# microzed_breakout_v0_7.net
KiCad netlist of a schematic drawn in EAGLE
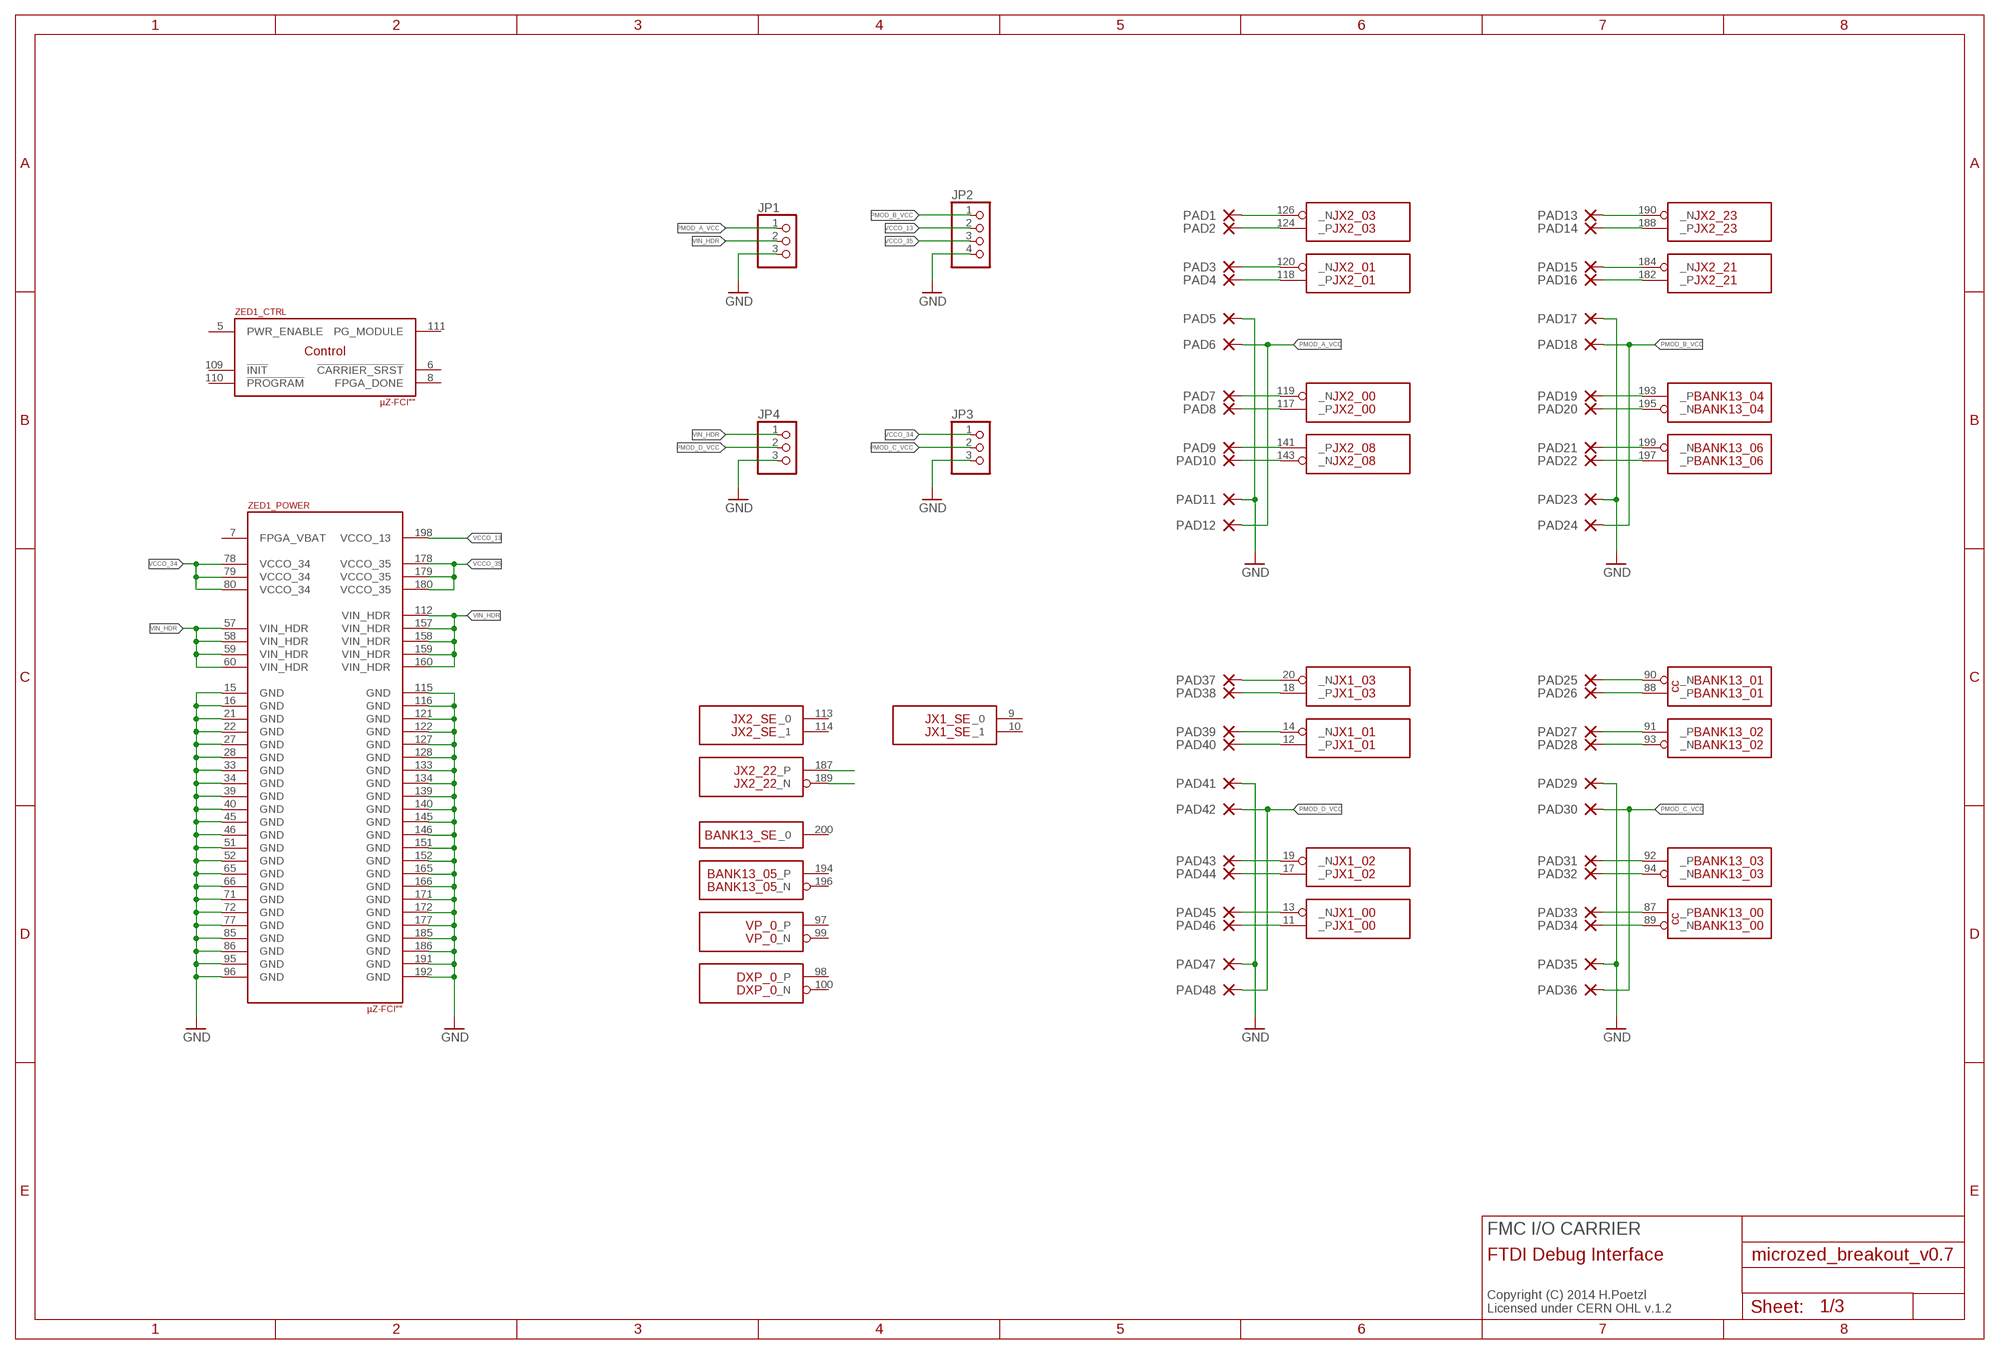
[diagram p0: schematic, sheet 1]
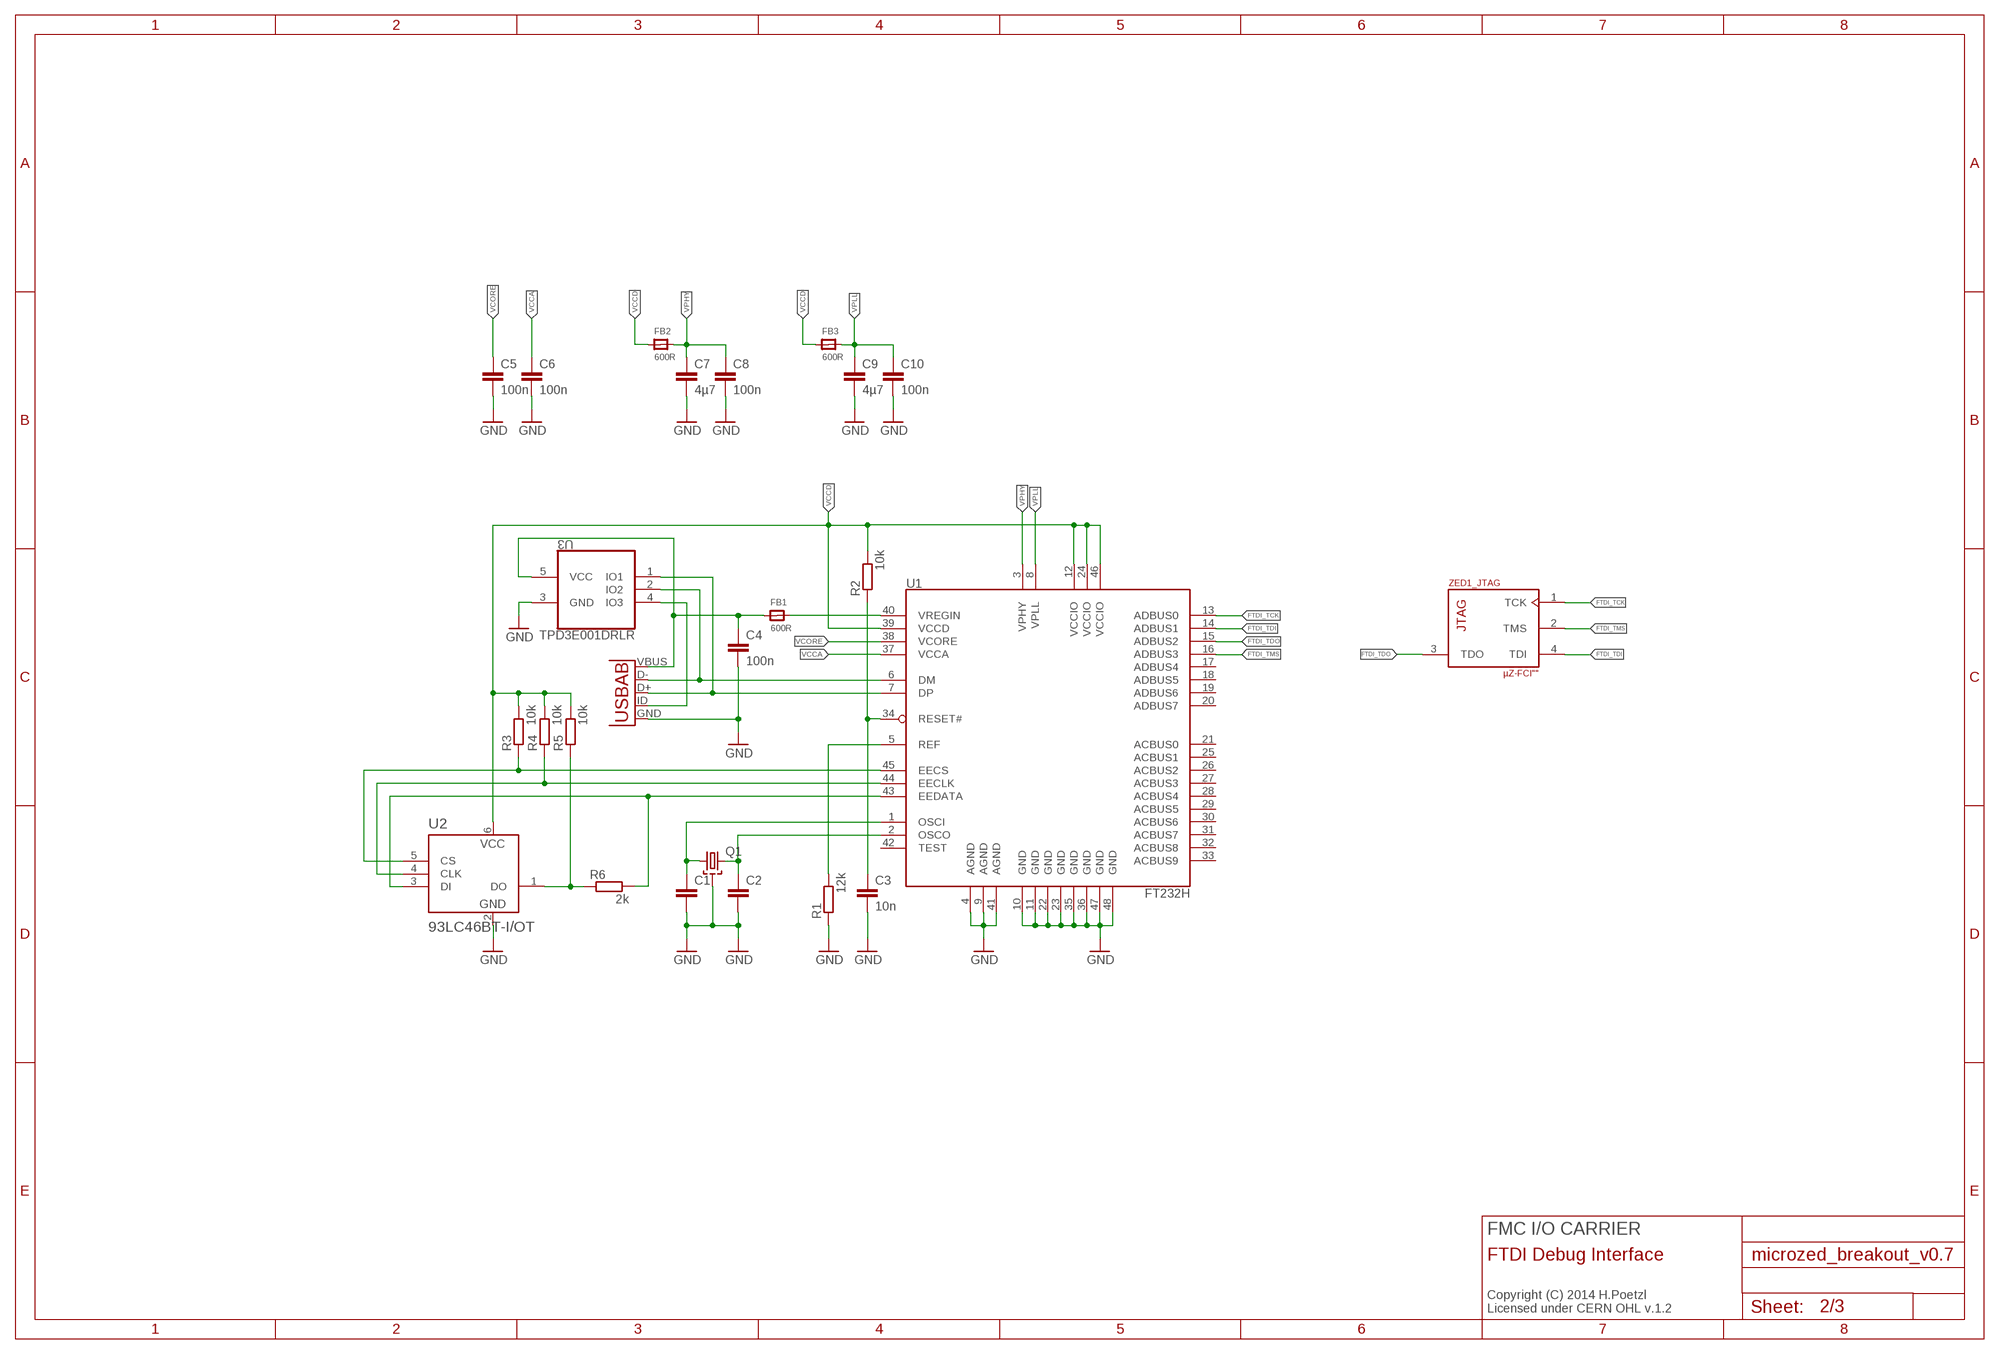
[diagram p1: schematic, sheet 2]
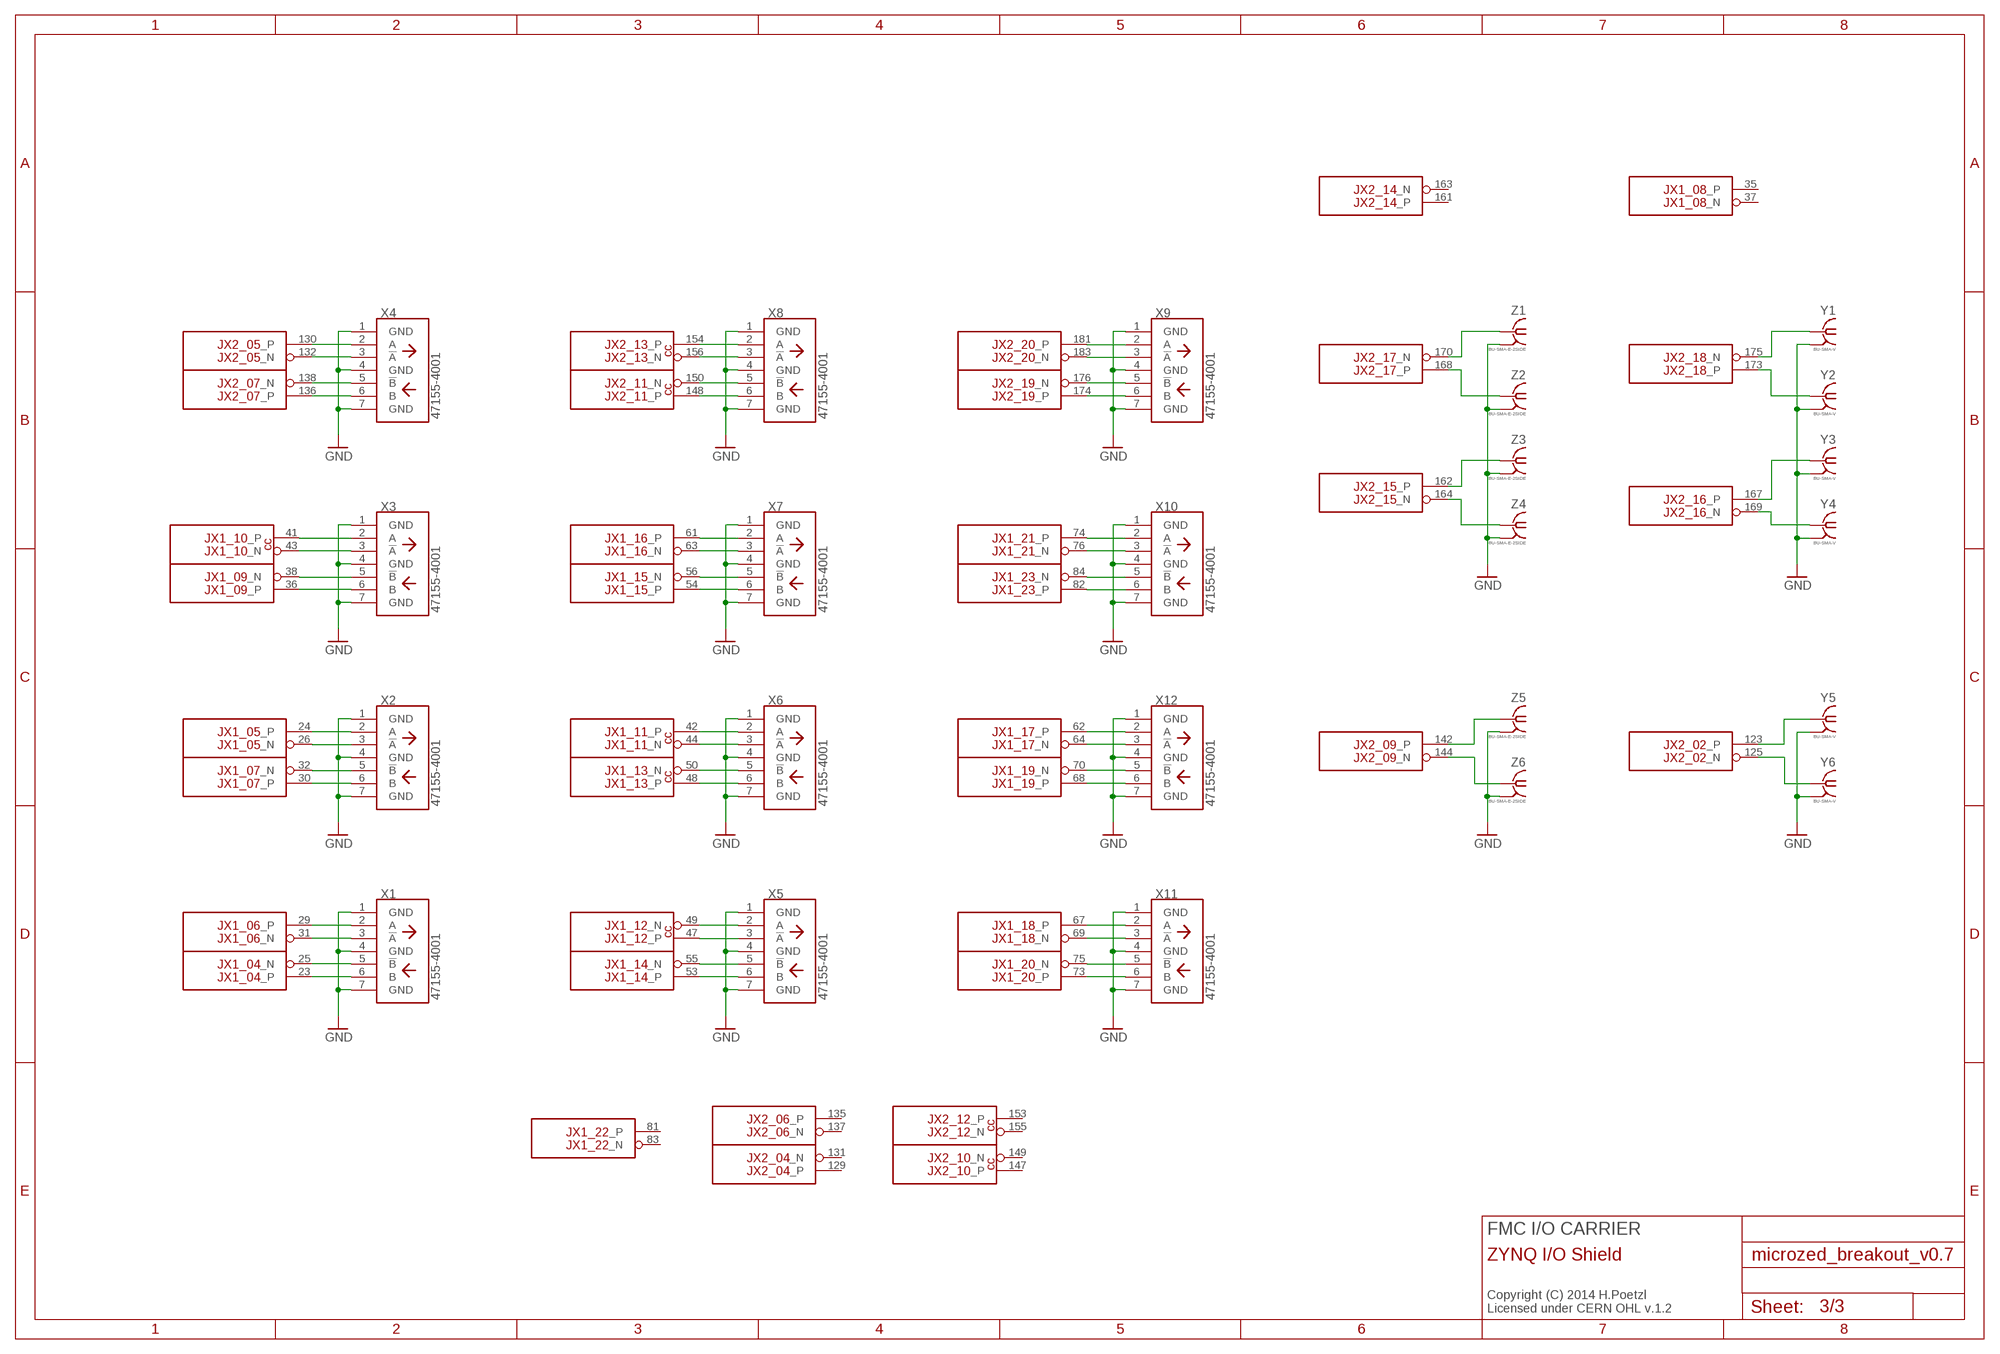
[diagram p2: schematic, sheet 3]

(export (version "E")
  (design (tool "Eeschema 10.0.6"))
  (components
    (comp (ref "X1")
      (value "47155-4001")
      (footprint "eagle-import:SATA7-VERT")
      (libsource (lib "eagle-import") (part "SATA7-VERT"))
    )
    (comp (ref "X2")
      (value "47155-4001")
      (footprint "eagle-import:SATA7-VERT")
      (libsource (lib "eagle-import") (part "SATA7-VERT"))
    )
    (comp (ref "X3")
      (value "47155-4001")
      (footprint "eagle-import:SATA7-VERT")
      (libsource (lib "eagle-import") (part "SATA7-VERT"))
    )
    (comp (ref "X4")
      (value "47155-4001")
      (footprint "eagle-import:SATA7-VERT")
      (libsource (lib "eagle-import") (part "SATA7-VERT"))
    )
    (comp (ref "X5")
      (value "47155-4001")
      (footprint "eagle-import:SATA7-VERT")
      (libsource (lib "eagle-import") (part "SATA7-VERT"))
    )
    (comp (ref "X6")
      (value "47155-4001")
      (footprint "eagle-import:SATA7-VERT")
      (libsource (lib "eagle-import") (part "SATA7-VERT"))
    )
    (comp (ref "X7")
      (value "47155-4001")
      (footprint "eagle-import:SATA7-VERT")
      (libsource (lib "eagle-import") (part "SATA7-VERT"))
    )
    (comp (ref "X8")
      (value "47155-4001")
      (footprint "eagle-import:SATA7-VERT")
      (libsource (lib "eagle-import") (part "SATA7-VERT"))
    )
    (comp (ref "X9")
      (value "47155-4001")
      (footprint "eagle-import:SATA7-VERT")
      (libsource (lib "eagle-import") (part "SATA7-VERT"))
    )
    (comp (ref "X10")
      (value "47155-4001")
      (footprint "eagle-import:SATA7-VERT")
      (libsource (lib "eagle-import") (part "SATA7-VERT"))
    )
    (comp (ref "X11")
      (value "47155-4001")
      (footprint "eagle-import:SATA7-VERT")
      (libsource (lib "eagle-import") (part "SATA7-VERT"))
    )
    (comp (ref "X12")
      (value "47155-4001")
      (footprint "eagle-import:SATA7-VERT")
      (libsource (lib "eagle-import") (part "SATA7-VERT"))
    )
    (comp (ref "Y1")
      (value "BU-SMA-V")
      (footprint "eagle-import:BU-SMA-V")
      (libsource (lib "eagle-import") (part "BU-SMA-V"))
    )
    (comp (ref "Y2")
      (value "BU-SMA-V")
      (footprint "eagle-import:BU-SMA-V")
      (libsource (lib "eagle-import") (part "BU-SMA-V"))
    )
    (comp (ref "Y3")
      (value "BU-SMA-V")
      (footprint "eagle-import:BU-SMA-V")
      (libsource (lib "eagle-import") (part "BU-SMA-V"))
    )
    (comp (ref "Y4")
      (value "BU-SMA-V")
      (footprint "eagle-import:BU-SMA-V")
      (libsource (lib "eagle-import") (part "BU-SMA-V"))
    )
    (comp (ref "Y5")
      (value "BU-SMA-V")
      (footprint "eagle-import:BU-SMA-V")
      (libsource (lib "eagle-import") (part "BU-SMA-V"))
    )
    (comp (ref "Y6")
      (value "BU-SMA-V")
      (footprint "eagle-import:BU-SMA-V")
      (libsource (lib "eagle-import") (part "BU-SMA-V"))
    )
    (comp (ref "Z1")
      (value "BU-SMA-E-2SIDE")
      (footprint "eagle-import:SMA_EDGE_2SIDE")
      (libsource (lib "eagle-import") (part "BU-SMA-E-2SIDE"))
    )
    (comp (ref "Z2")
      (value "BU-SMA-E-2SIDE")
      (footprint "eagle-import:SMA_EDGE_2SIDE")
      (libsource (lib "eagle-import") (part "BU-SMA-E-2SIDE"))
    )
    (comp (ref "Z3")
      (value "BU-SMA-E-2SIDE")
      (footprint "eagle-import:SMA_EDGE_2SIDE")
      (libsource (lib "eagle-import") (part "BU-SMA-E-2SIDE"))
    )
    (comp (ref "Z4")
      (value "BU-SMA-E-2SIDE")
      (footprint "eagle-import:SMA_EDGE_2SIDE")
      (libsource (lib "eagle-import") (part "BU-SMA-E-2SIDE"))
    )
    (comp (ref "Z5")
      (value "BU-SMA-E-2SIDE")
      (footprint "eagle-import:SMA_EDGE_2SIDE")
      (libsource (lib "eagle-import") (part "BU-SMA-E-2SIDE"))
    )
    (comp (ref "Z6")
      (value "BU-SMA-E-2SIDE")
      (footprint "eagle-import:SMA_EDGE_2SIDE")
      (libsource (lib "eagle-import") (part "BU-SMA-E-2SIDE"))
    )
    (comp (ref "ZED1")
      (value "µZ-FCI\"\"")
      (footprint "eagle-import:µZ")
      (libsource (lib "eagle-import") (part "µZ-FCI{dblquote}{dblquote}"))
    )
    (comp (ref "C1")
      (value "C-EUC0402K")
      (footprint "eagle-import:C0402K")
      (libsource (lib "eagle-import") (part "C-EUC0402K"))
    )
    (comp (ref "C2")
      (value "C-EUC0402K")
      (footprint "eagle-import:C0402K")
      (libsource (lib "eagle-import") (part "C-EUC0402K"))
    )
    (comp (ref "C3")
      (value "10n")
      (footprint "eagle-import:C0402K")
      (libsource (lib "eagle-import") (part "C-EUC0402K"))
    )
    (comp (ref "C4")
      (value "100n")
      (footprint "eagle-import:C0402K")
      (libsource (lib "eagle-import") (part "C-EUC0402K"))
    )
    (comp (ref "C5")
      (value "100n")
      (footprint "eagle-import:C0402K")
      (libsource (lib "eagle-import") (part "C-EUC0402K"))
    )
    (comp (ref "C6")
      (value "100n")
      (footprint "eagle-import:C0402K")
      (libsource (lib "eagle-import") (part "C-EUC0402K"))
    )
    (comp (ref "C7")
      (value "4µ7")
      (footprint "eagle-import:C0402K")
      (libsource (lib "eagle-import") (part "C-EUC0402K"))
    )
    (comp (ref "C8")
      (value "100n")
      (footprint "eagle-import:C0402K")
      (libsource (lib "eagle-import") (part "C-EUC0402K"))
    )
    (comp (ref "C9")
      (value "4µ7")
      (footprint "eagle-import:C0402K")
      (libsource (lib "eagle-import") (part "C-EUC0402K"))
    )
    (comp (ref "C10")
      (value "100n")
      (footprint "eagle-import:C0402K")
      (libsource (lib "eagle-import") (part "C-EUC0402K"))
    )
    (comp (ref "FB1")
      (value "600R")
      (footprint "eagle-import:_0603MP")
      (libsource (lib "eagle-import") (part "FERRITE_0603MP"))
    )
    (comp (ref "FB2")
      (value "600R")
      (footprint "eagle-import:_0603MP")
      (libsource (lib "eagle-import") (part "FERRITE_0603MP"))
    )
    (comp (ref "FB3")
      (value "600R")
      (footprint "eagle-import:_0603MP")
      (libsource (lib "eagle-import") (part "FERRITE_0603MP"))
    )
    (comp (ref "Q1")
      (value "SMD-4P-2G-3.2X2.5")
      (footprint "eagle-import:ABM8G")
      (libsource (lib "eagle-import") (part "SMD-4P-2G-3.2X2.5"))
    )
    (comp (ref "R1")
      (value "12k")
      (footprint "eagle-import:R0402")
      (libsource (lib "eagle-import") (part "R-EU_R0402"))
    )
    (comp (ref "R2")
      (value "10k")
      (footprint "eagle-import:R0402")
      (libsource (lib "eagle-import") (part "R-EU_R0402"))
    )
    (comp (ref "R3")
      (value "10k")
      (footprint "eagle-import:R0402")
      (libsource (lib "eagle-import") (part "R-EU_R0402"))
    )
    (comp (ref "R4")
      (value "10k")
      (footprint "eagle-import:R0402")
      (libsource (lib "eagle-import") (part "R-EU_R0402"))
    )
    (comp (ref "R5")
      (value "10k")
      (footprint "eagle-import:R0402")
      (libsource (lib "eagle-import") (part "R-EU_R0402"))
    )
    (comp (ref "R6")
      (value "2k")
      (footprint "eagle-import:R0402")
      (libsource (lib "eagle-import") (part "R-EU_R0402"))
    )
    (comp (ref "U1")
      (value "FT232H")
      (footprint "eagle-import:LQFP48")
      (libsource (lib "eagle-import") (part "FT232H"))
    )
    (comp (ref "U2")
      (value "93LC46BT-I/OT")
      (footprint "eagle-import:SOT95P280X145-6N")
      (libsource (lib "eagle-import") (part "93LC46BT-I/OT"))
    )
    (comp (ref "U3")
      (value "TPD3E001DRLR")
      (footprint "eagle-import:SOT50P160X60-5N")
      (libsource (lib "eagle-import") (part "TPD3E001DRLR"))
    )
    (comp (ref "USB")
      (value "USB-AB")
      (footprint "eagle-import:USB-AB-MICRO-SMD")
      (libsource (lib "eagle-import") (part "USB-AB"))
    )
    (comp (ref "JP1")
      (value "PINHD-1X03_2.54")
      (footprint "eagle-import:1X03")
      (libsource (lib "eagle-import") (part "PINHD-1X03_2.54"))
    )
    (comp (ref "JP2")
      (value "PINHD-1X04_2.54")
      (footprint "eagle-import:1X04")
      (libsource (lib "eagle-import") (part "PINHD-1X04_2.54"))
    )
    (comp (ref "JP3")
      (value "PINHD-1X03_2.54")
      (footprint "eagle-import:1X03")
      (libsource (lib "eagle-import") (part "PINHD-1X03_2.54"))
    )
    (comp (ref "JP4")
      (value "PINHD-1X03_2.54")
      (footprint "eagle-import:1X03")
      (libsource (lib "eagle-import") (part "PINHD-1X03_2.54"))
    )
    (comp (ref "PAD1")
      (value "SMD-PAD1.6X3.8MM-U")
      (footprint "eagle-import:1.6X3.8U-MM")
      (libsource (lib "eagle-import") (part "SMD-PAD1.6X3.8MM-U"))
    )
    (comp (ref "PAD2")
      (value "SMD-PAD1.6X3.8MM-U")
      (footprint "eagle-import:1.6X3.8U-MM")
      (libsource (lib "eagle-import") (part "SMD-PAD1.6X3.8MM-U"))
    )
    (comp (ref "PAD3")
      (value "SMD-PAD1.6X3.8MM-U")
      (footprint "eagle-import:1.6X3.8U-MM")
      (libsource (lib "eagle-import") (part "SMD-PAD1.6X3.8MM-U"))
    )
    (comp (ref "PAD4")
      (value "SMD-PAD1.6X3.8MM-U")
      (footprint "eagle-import:1.6X3.8U-MM")
      (libsource (lib "eagle-import") (part "SMD-PAD1.6X3.8MM-U"))
    )
    (comp (ref "PAD5")
      (value "SMD-PAD1.6X3.8MM-U")
      (footprint "eagle-import:1.6X3.8U-MM")
      (libsource (lib "eagle-import") (part "SMD-PAD1.6X3.8MM-U"))
    )
    (comp (ref "PAD6")
      (value "SMD-PAD1.6X3.8MM-U")
      (footprint "eagle-import:1.6X3.8U-MM")
      (libsource (lib "eagle-import") (part "SMD-PAD1.6X3.8MM-U"))
    )
    (comp (ref "PAD7")
      (value "SMD-PAD1.6X3.8MM-U")
      (footprint "eagle-import:1.6X3.8U-MM")
      (libsource (lib "eagle-import") (part "SMD-PAD1.6X3.8MM-U"))
    )
    (comp (ref "PAD8")
      (value "SMD-PAD1.6X3.8MM-U")
      (footprint "eagle-import:1.6X3.8U-MM")
      (libsource (lib "eagle-import") (part "SMD-PAD1.6X3.8MM-U"))
    )
    (comp (ref "PAD9")
      (value "SMD-PAD1.6X3.8MM-U")
      (footprint "eagle-import:1.6X3.8U-MM")
      (libsource (lib "eagle-import") (part "SMD-PAD1.6X3.8MM-U"))
    )
    (comp (ref "PAD10")
      (value "SMD-PAD1.6X3.8MM-U")
      (footprint "eagle-import:1.6X3.8U-MM")
      (libsource (lib "eagle-import") (part "SMD-PAD1.6X3.8MM-U"))
    )
    (comp (ref "PAD11")
      (value "SMD-PAD1.6X3.8MM-U")
      (footprint "eagle-import:1.6X3.8U-MM")
      (libsource (lib "eagle-import") (part "SMD-PAD1.6X3.8MM-U"))
    )
    (comp (ref "PAD12")
      (value "SMD-PAD1.6X3.8MM-U")
      (footprint "eagle-import:1.6X3.8U-MM")
      (libsource (lib "eagle-import") (part "SMD-PAD1.6X3.8MM-U"))
    )
    (comp (ref "PAD13")
      (value "SMD-PAD1.6X3.8MM-U")
      (footprint "eagle-import:1.6X3.8U-MM")
      (libsource (lib "eagle-import") (part "SMD-PAD1.6X3.8MM-U"))
    )
    (comp (ref "PAD14")
      (value "SMD-PAD1.6X3.8MM-U")
      (footprint "eagle-import:1.6X3.8U-MM")
      (libsource (lib "eagle-import") (part "SMD-PAD1.6X3.8MM-U"))
    )
    (comp (ref "PAD15")
      (value "SMD-PAD1.6X3.8MM-U")
      (footprint "eagle-import:1.6X3.8U-MM")
      (libsource (lib "eagle-import") (part "SMD-PAD1.6X3.8MM-U"))
    )
    (comp (ref "PAD16")
      (value "SMD-PAD1.6X3.8MM-U")
      (footprint "eagle-import:1.6X3.8U-MM")
      (libsource (lib "eagle-import") (part "SMD-PAD1.6X3.8MM-U"))
    )
    (comp (ref "PAD17")
      (value "SMD-PAD1.6X3.8MM-U")
      (footprint "eagle-import:1.6X3.8U-MM")
      (libsource (lib "eagle-import") (part "SMD-PAD1.6X3.8MM-U"))
    )
    (comp (ref "PAD18")
      (value "SMD-PAD1.6X3.8MM-U")
      (footprint "eagle-import:1.6X3.8U-MM")
      (libsource (lib "eagle-import") (part "SMD-PAD1.6X3.8MM-U"))
    )
    (comp (ref "PAD19")
      (value "SMD-PAD1.6X3.8MM-U")
      (footprint "eagle-import:1.6X3.8U-MM")
      (libsource (lib "eagle-import") (part "SMD-PAD1.6X3.8MM-U"))
    )
    (comp (ref "PAD20")
      (value "SMD-PAD1.6X3.8MM-U")
      (footprint "eagle-import:1.6X3.8U-MM")
      (libsource (lib "eagle-import") (part "SMD-PAD1.6X3.8MM-U"))
    )
    (comp (ref "PAD21")
      (value "SMD-PAD1.6X3.8MM-U")
      (footprint "eagle-import:1.6X3.8U-MM")
      (libsource (lib "eagle-import") (part "SMD-PAD1.6X3.8MM-U"))
    )
    (comp (ref "PAD22")
      (value "SMD-PAD1.6X3.8MM-U")
      (footprint "eagle-import:1.6X3.8U-MM")
      (libsource (lib "eagle-import") (part "SMD-PAD1.6X3.8MM-U"))
    )
    (comp (ref "PAD23")
      (value "SMD-PAD1.6X3.8MM-U")
      (footprint "eagle-import:1.6X3.8U-MM")
      (libsource (lib "eagle-import") (part "SMD-PAD1.6X3.8MM-U"))
    )
    (comp (ref "PAD24")
      (value "SMD-PAD1.6X3.8MM-U")
      (footprint "eagle-import:1.6X3.8U-MM")
      (libsource (lib "eagle-import") (part "SMD-PAD1.6X3.8MM-U"))
    )
    (comp (ref "PAD25")
      (value "SMD-PAD1.6X3.8MM-U")
      (footprint "eagle-import:1.6X3.8U-MM")
      (libsource (lib "eagle-import") (part "SMD-PAD1.6X3.8MM-U"))
    )
    (comp (ref "PAD26")
      (value "SMD-PAD1.6X3.8MM-U")
      (footprint "eagle-import:1.6X3.8U-MM")
      (libsource (lib "eagle-import") (part "SMD-PAD1.6X3.8MM-U"))
    )
    (comp (ref "PAD27")
      (value "SMD-PAD1.6X3.8MM-U")
      (footprint "eagle-import:1.6X3.8U-MM")
      (libsource (lib "eagle-import") (part "SMD-PAD1.6X3.8MM-U"))
    )
    (comp (ref "PAD28")
      (value "SMD-PAD1.6X3.8MM-U")
      (footprint "eagle-import:1.6X3.8U-MM")
      (libsource (lib "eagle-import") (part "SMD-PAD1.6X3.8MM-U"))
    )
    (comp (ref "PAD29")
      (value "SMD-PAD1.6X3.8MM-U")
      (footprint "eagle-import:1.6X3.8U-MM")
      (libsource (lib "eagle-import") (part "SMD-PAD1.6X3.8MM-U"))
    )
    (comp (ref "PAD30")
      (value "SMD-PAD1.6X3.8MM-U")
      (footprint "eagle-import:1.6X3.8U-MM")
      (libsource (lib "eagle-import") (part "SMD-PAD1.6X3.8MM-U"))
    )
    (comp (ref "PAD31")
      (value "SMD-PAD1.6X3.8MM-U")
      (footprint "eagle-import:1.6X3.8U-MM")
      (libsource (lib "eagle-import") (part "SMD-PAD1.6X3.8MM-U"))
    )
    (comp (ref "PAD32")
      (value "SMD-PAD1.6X3.8MM-U")
      (footprint "eagle-import:1.6X3.8U-MM")
      (libsource (lib "eagle-import") (part "SMD-PAD1.6X3.8MM-U"))
    )
    (comp (ref "PAD33")
      (value "SMD-PAD1.6X3.8MM-U")
      (footprint "eagle-import:1.6X3.8U-MM")
      (libsource (lib "eagle-import") (part "SMD-PAD1.6X3.8MM-U"))
    )
    (comp (ref "PAD34")
      (value "SMD-PAD1.6X3.8MM-U")
      (footprint "eagle-import:1.6X3.8U-MM")
      (libsource (lib "eagle-import") (part "SMD-PAD1.6X3.8MM-U"))
    )
    (comp (ref "PAD35")
      (value "SMD-PAD1.6X3.8MM-U")
      (footprint "eagle-import:1.6X3.8U-MM")
      (libsource (lib "eagle-import") (part "SMD-PAD1.6X3.8MM-U"))
    )
    (comp (ref "PAD36")
      (value "SMD-PAD1.6X3.8MM-U")
      (footprint "eagle-import:1.6X3.8U-MM")
      (libsource (lib "eagle-import") (part "SMD-PAD1.6X3.8MM-U"))
    )
    (comp (ref "PAD37")
      (value "SMD-PAD1.6X3.8MM-U")
      (footprint "eagle-import:1.6X3.8U-MM")
      (libsource (lib "eagle-import") (part "SMD-PAD1.6X3.8MM-U"))
    )
    (comp (ref "PAD38")
      (value "SMD-PAD1.6X3.8MM-U")
      (footprint "eagle-import:1.6X3.8U-MM")
      (libsource (lib "eagle-import") (part "SMD-PAD1.6X3.8MM-U"))
    )
    (comp (ref "PAD39")
      (value "SMD-PAD1.6X3.8MM-U")
      (footprint "eagle-import:1.6X3.8U-MM")
      (libsource (lib "eagle-import") (part "SMD-PAD1.6X3.8MM-U"))
    )
    (comp (ref "PAD40")
      (value "SMD-PAD1.6X3.8MM-U")
      (footprint "eagle-import:1.6X3.8U-MM")
      (libsource (lib "eagle-import") (part "SMD-PAD1.6X3.8MM-U"))
    )
    (comp (ref "PAD41")
      (value "SMD-PAD1.6X3.8MM-U")
      (footprint "eagle-import:1.6X3.8U-MM")
      (libsource (lib "eagle-import") (part "SMD-PAD1.6X3.8MM-U"))
    )
    (comp (ref "PAD42")
      (value "SMD-PAD1.6X3.8MM-U")
      (footprint "eagle-import:1.6X3.8U-MM")
      (libsource (lib "eagle-import") (part "SMD-PAD1.6X3.8MM-U"))
    )
    (comp (ref "PAD43")
      (value "SMD-PAD1.6X3.8MM-U")
      (footprint "eagle-import:1.6X3.8U-MM")
      (libsource (lib "eagle-import") (part "SMD-PAD1.6X3.8MM-U"))
    )
    (comp (ref "PAD44")
      (value "SMD-PAD1.6X3.8MM-U")
      (footprint "eagle-import:1.6X3.8U-MM")
      (libsource (lib "eagle-import") (part "SMD-PAD1.6X3.8MM-U"))
    )
    (comp (ref "PAD45")
      (value "SMD-PAD1.6X3.8MM-U")
      (footprint "eagle-import:1.6X3.8U-MM")
      (libsource (lib "eagle-import") (part "SMD-PAD1.6X3.8MM-U"))
    )
    (comp (ref "PAD46")
      (value "SMD-PAD1.6X3.8MM-U")
      (footprint "eagle-import:1.6X3.8U-MM")
      (libsource (lib "eagle-import") (part "SMD-PAD1.6X3.8MM-U"))
    )
    (comp (ref "PAD47")
      (value "SMD-PAD1.6X3.8MM-U")
      (footprint "eagle-import:1.6X3.8U-MM")
      (libsource (lib "eagle-import") (part "SMD-PAD1.6X3.8MM-U"))
    )
    (comp (ref "PAD48")
      (value "SMD-PAD1.6X3.8MM-U")
      (footprint "eagle-import:1.6X3.8U-MM")
      (libsource (lib "eagle-import") (part "SMD-PAD1.6X3.8MM-U"))
    )
  )
  (nets
    (net (code "1") (name "FPGA_VBAT") (class "Default")
      (node (ref "ZED1") (pin "7") (pinfunction "FPGA_VBAT_7") (pintype "power_in"))
    )
    (net (code "2") (name "FTDI_TCK") (class "Default")
      (node (ref "U1") (pin "13") (pinfunction "ADBUS0_13") (pintype "output"))
      (node (ref "ZED1") (pin "1") (pinfunction "TCK_1") (pintype "output"))
    )
    (net (code "3") (name "FTDI_TDI") (class "Default")
      (node (ref "U1") (pin "14") (pinfunction "ADBUS1_14") (pintype "input"))
      (node (ref "ZED1") (pin "4") (pinfunction "TDI_4") (pintype "output"))
    )
    (net (code "4") (name "FTDI_TDO") (class "Default")
      (node (ref "U1") (pin "15") (pinfunction "ADBUS2_15") (pintype "output"))
      (node (ref "ZED1") (pin "3") (pinfunction "TDO_3") (pintype "input"))
    )
    (net (code "5") (name "FTDI_TMS") (class "Default")
      (node (ref "U1") (pin "16") (pinfunction "ADBUS3_16") (pintype "input"))
      (node (ref "ZED1") (pin "2") (pinfunction "TMS_2") (pintype "output"))
    )
    (net (code "6") (name "GND") (class "Default")
      (node (ref "C1") (pin "2") (pinfunction "2_2") (pintype "passive"))
      (node (ref "C10") (pin "2") (pinfunction "2_2") (pintype "passive"))
      (node (ref "C2") (pin "2") (pinfunction "2_2") (pintype "passive"))
      (node (ref "C3") (pin "2") (pinfunction "2_2") (pintype "passive"))
      (node (ref "C4") (pin "2") (pinfunction "2_2") (pintype "passive"))
      (node (ref "C5") (pin "2") (pinfunction "2_2") (pintype "passive"))
      (node (ref "C6") (pin "2") (pinfunction "2_2") (pintype "passive"))
      (node (ref "C7") (pin "2") (pinfunction "2_2") (pintype "passive"))
      (node (ref "C8") (pin "2") (pinfunction "2_2") (pintype "passive"))
      (node (ref "C9") (pin "2") (pinfunction "2_2") (pintype "passive"))
      (node (ref "JP1") (pin "3") (pinfunction "3_3") (pintype "passive"))
      (node (ref "JP2") (pin "4") (pinfunction "4_4") (pintype "passive"))
      (node (ref "JP3") (pin "3") (pinfunction "3_3") (pintype "passive"))
      (node (ref "JP4") (pin "3") (pinfunction "3_3") (pintype "passive"))
      (node (ref "PAD11") (pin "1") (pinfunction "P_1") (pintype "passive"))
      (node (ref "PAD17") (pin "1") (pinfunction "P_1") (pintype "passive"))
      (node (ref "PAD23") (pin "1") (pinfunction "P_1") (pintype "passive"))
      (node (ref "PAD29") (pin "1") (pinfunction "P_1") (pintype "passive"))
      (node (ref "PAD35") (pin "1") (pinfunction "P_1") (pintype "passive"))
      (node (ref "PAD41") (pin "1") (pinfunction "P_1") (pintype "passive"))
      (node (ref "PAD47") (pin "1") (pinfunction "P_1") (pintype "passive"))
      (node (ref "PAD5") (pin "1") (pinfunction "P_1") (pintype "passive"))
      (node (ref "Q1") (pin "2") (pinfunction "GND_2") (pintype "power_in"))
      (node (ref "Q1") (pin "4") (pinfunction "GND_4") (pintype "power_in"))
      (node (ref "R1") (pin "1") (pinfunction "1_1") (pintype "passive"))
      (node (ref "U1") (pin "10") (pinfunction "GND_10") (pintype "power_in"))
      (node (ref "U1") (pin "11") (pinfunction "GND_11") (pintype "power_in"))
      (node (ref "U1") (pin "22") (pinfunction "GND_22") (pintype "power_in"))
      (node (ref "U1") (pin "23") (pinfunction "GND_23") (pintype "power_in"))
      (node (ref "U1") (pin "35") (pinfunction "GND_35") (pintype "power_in"))
      (node (ref "U1") (pin "36") (pinfunction "GND_36") (pintype "power_in"))
      (node (ref "U1") (pin "4") (pinfunction "AGND_4") (pintype "power_in"))
      (node (ref "U1") (pin "41") (pinfunction "AGND_41") (pintype "power_in"))
      (node (ref "U1") (pin "47") (pinfunction "GND_47") (pintype "power_in"))
      (node (ref "U1") (pin "48") (pinfunction "GND_48") (pintype "power_in"))
      (node (ref "U1") (pin "9") (pinfunction "AGND_9") (pintype "power_in"))
      (node (ref "U2") (pin "2") (pinfunction "VSS_2") (pintype "power_in"))
      (node (ref "U3") (pin "3") (pinfunction "GND_3") (pintype "passive"))
      (node (ref "USB") (pin "GND") (pinfunction "GND_GND") (pintype "bidirectional"))
      (node (ref "X1") (pin "1") (pinfunction "GND_1") (pintype "passive"))
      (node (ref "X1") (pin "4") (pinfunction "GND_4") (pintype "passive"))
      (node (ref "X1") (pin "7") (pinfunction "GND_7") (pintype "passive"))
      (node (ref "X10") (pin "1") (pinfunction "GND_1") (pintype "passive"))
      (node (ref "X10") (pin "4") (pinfunction "GND_4") (pintype "passive"))
      (node (ref "X10") (pin "7") (pinfunction "GND_7") (pintype "passive"))
      (node (ref "X11") (pin "1") (pinfunction "GND_1") (pintype "passive"))
      (node (ref "X11") (pin "4") (pinfunction "GND_4") (pintype "passive"))
      (node (ref "X11") (pin "7") (pinfunction "GND_7") (pintype "passive"))
      (node (ref "X12") (pin "1") (pinfunction "GND_1") (pintype "passive"))
      (node (ref "X12") (pin "4") (pinfunction "GND_4") (pintype "passive"))
      (node (ref "X12") (pin "7") (pinfunction "GND_7") (pintype "passive"))
      (node (ref "X2") (pin "1") (pinfunction "GND_1") (pintype "passive"))
      (node (ref "X2") (pin "4") (pinfunction "GND_4") (pintype "passive"))
      (node (ref "X2") (pin "7") (pinfunction "GND_7") (pintype "passive"))
      (node (ref "X3") (pin "1") (pinfunction "GND_1") (pintype "passive"))
      (node (ref "X3") (pin "4") (pinfunction "GND_4") (pintype "passive"))
      (node (ref "X3") (pin "7") (pinfunction "GND_7") (pintype "passive"))
      (node (ref "X4") (pin "1") (pinfunction "GND_1") (pintype "passive"))
      (node (ref "X4") (pin "4") (pinfunction "GND_4") (pintype "passive"))
      (node (ref "X4") (pin "7") (pinfunction "GND_7") (pintype "passive"))
      (node (ref "X5") (pin "1") (pinfunction "GND_1") (pintype "passive"))
      (node (ref "X5") (pin "4") (pinfunction "GND_4") (pintype "passive"))
      (node (ref "X5") (pin "7") (pinfunction "GND_7") (pintype "passive"))
      (node (ref "X6") (pin "1") (pinfunction "GND_1") (pintype "passive"))
      (node (ref "X6") (pin "4") (pinfunction "GND_4") (pintype "passive"))
      (node (ref "X6") (pin "7") (pinfunction "GND_7") (pintype "passive"))
      (node (ref "X7") (pin "1") (pinfunction "GND_1") (pintype "passive"))
      (node (ref "X7") (pin "4") (pinfunction "GND_4") (pintype "passive"))
      (node (ref "X7") (pin "7") (pinfunction "GND_7") (pintype "passive"))
      (node (ref "X8") (pin "1") (pinfunction "GND_1") (pintype "passive"))
      (node (ref "X8") (pin "4") (pinfunction "GND_4") (pintype "passive"))
      (node (ref "X8") (pin "7") (pinfunction "GND_7") (pintype "passive"))
      (node (ref "X9") (pin "1") (pinfunction "GND_1") (pintype "passive"))
      (node (ref "X9") (pin "4") (pinfunction "GND_4") (pintype "passive"))
      (node (ref "X9") (pin "7") (pinfunction "GND_7") (pintype "passive"))
      (node (ref "Y1") (pin "2") (pinfunction "2_2") (pintype "passive"))
      (node (ref "Y1") (pin "3") (pinfunction "2_3") (pintype "passive"))
      (node (ref "Y1") (pin "4") (pinfunction "2_4") (pintype "passive"))
      (node (ref "Y1") (pin "5") (pinfunction "2_5") (pintype "passive"))
      (node (ref "Y2") (pin "2") (pinfunction "2_2") (pintype "passive"))
      (node (ref "Y2") (pin "3") (pinfunction "2_3") (pintype "passive"))
      (node (ref "Y2") (pin "4") (pinfunction "2_4") (pintype "passive"))
      (node (ref "Y2") (pin "5") (pinfunction "2_5") (pintype "passive"))
      (node (ref "Y3") (pin "2") (pinfunction "2_2") (pintype "passive"))
      (node (ref "Y3") (pin "3") (pinfunction "2_3") (pintype "passive"))
      (node (ref "Y3") (pin "4") (pinfunction "2_4") (pintype "passive"))
      (node (ref "Y3") (pin "5") (pinfunction "2_5") (pintype "passive"))
      (node (ref "Y4") (pin "2") (pinfunction "2_2") (pintype "passive"))
      (node (ref "Y4") (pin "3") (pinfunction "2_3") (pintype "passive"))
      (node (ref "Y4") (pin "4") (pinfunction "2_4") (pintype "passive"))
      (node (ref "Y4") (pin "5") (pinfunction "2_5") (pintype "passive"))
      (node (ref "Y5") (pin "2") (pinfunction "2_2") (pintype "passive"))
      (node (ref "Y5") (pin "3") (pinfunction "2_3") (pintype "passive"))
      (node (ref "Y5") (pin "4") (pinfunction "2_4") (pintype "passive"))
      (node (ref "Y5") (pin "5") (pinfunction "2_5") (pintype "passive"))
      (node (ref "Y6") (pin "2") (pinfunction "2_2") (pintype "passive"))
      (node (ref "Y6") (pin "3") (pinfunction "2_3") (pintype "passive"))
      (node (ref "Y6") (pin "4") (pinfunction "2_4") (pintype "passive"))
      (node (ref "Y6") (pin "5") (pinfunction "2_5") (pintype "passive"))
      (node (ref "Z1") (pin "2@1") (pinfunction "2_2@1") (pintype "passive"))
      (node (ref "Z1") (pin "2@2") (pinfunction "2_2@2") (pintype "passive"))
      (node (ref "Z1") (pin "2@3") (pinfunction "2_2@3") (pintype "passive"))
      (node (ref "Z1") (pin "2@4") (pinfunction "2_2@4") (pintype "passive"))
      (node (ref "Z2") (pin "2@1") (pinfunction "2_2@1") (pintype "passive"))
      (node (ref "Z2") (pin "2@2") (pinfunction "2_2@2") (pintype "passive"))
      (node (ref "Z2") (pin "2@3") (pinfunction "2_2@3") (pintype "passive"))
      (node (ref "Z2") (pin "2@4") (pinfunction "2_2@4") (pintype "passive"))
      (node (ref "Z3") (pin "2@1") (pinfunction "2_2@1") (pintype "passive"))
      (node (ref "Z3") (pin "2@2") (pinfunction "2_2@2") (pintype "passive"))
      (node (ref "Z3") (pin "2@3") (pinfunction "2_2@3") (pintype "passive"))
      (node (ref "Z3") (pin "2@4") (pinfunction "2_2@4") (pintype "passive"))
      (node (ref "Z4") (pin "2@1") (pinfunction "2_2@1") (pintype "passive"))
      (node (ref "Z4") (pin "2@2") (pinfunction "2_2@2") (pintype "passive"))
      (node (ref "Z4") (pin "2@3") (pinfunction "2_2@3") (pintype "passive"))
      (node (ref "Z4") (pin "2@4") (pinfunction "2_2@4") (pintype "passive"))
      (node (ref "Z5") (pin "2@1") (pinfunction "2_2@1") (pintype "passive"))
      (node (ref "Z5") (pin "2@2") (pinfunction "2_2@2") (pintype "passive"))
      (node (ref "Z5") (pin "2@3") (pinfunction "2_2@3") (pintype "passive"))
      (node (ref "Z5") (pin "2@4") (pinfunction "2_2@4") (pintype "passive"))
      (node (ref "Z6") (pin "2@1") (pinfunction "2_2@1") (pintype "passive"))
      (node (ref "Z6") (pin "2@2") (pinfunction "2_2@2") (pintype "passive"))
      (node (ref "Z6") (pin "2@3") (pinfunction "2_2@3") (pintype "passive"))
      (node (ref "Z6") (pin "2@4") (pinfunction "2_2@4") (pintype "passive"))
      (node (ref "ZED1") (pin "115") (pinfunction "GND_115") (pintype "power_in"))
      (node (ref "ZED1") (pin "116") (pinfunction "GND_116") (pintype "power_in"))
      (node (ref "ZED1") (pin "121") (pinfunction "GND_121") (pintype "power_in"))
      (node (ref "ZED1") (pin "122") (pinfunction "GND_122") (pintype "power_in"))
      (node (ref "ZED1") (pin "127") (pinfunction "GND_127") (pintype "power_in"))
      (node (ref "ZED1") (pin "128") (pinfunction "GND_128") (pintype "power_in"))
      (node (ref "ZED1") (pin "133") (pinfunction "GND_133") (pintype "power_in"))
      (node (ref "ZED1") (pin "134") (pinfunction "GND_134") (pintype "power_in"))
      (node (ref "ZED1") (pin "139") (pinfunction "GND_139") (pintype "power_in"))
      (node (ref "ZED1") (pin "140") (pinfunction "GND_140") (pintype "power_in"))
      (node (ref "ZED1") (pin "145") (pinfunction "GND_145") (pintype "power_in"))
      (node (ref "ZED1") (pin "146") (pinfunction "GND_146") (pintype "power_in"))
      (node (ref "ZED1") (pin "15") (pinfunction "GND_15") (pintype "power_in"))
      (node (ref "ZED1") (pin "151") (pinfunction "GND_151") (pintype "power_in"))
      (node (ref "ZED1") (pin "152") (pinfunction "GND_152") (pintype "power_in"))
      (node (ref "ZED1") (pin "16") (pinfunction "GND_16") (pintype "power_in"))
      (node (ref "ZED1") (pin "165") (pinfunction "GND_165") (pintype "power_in"))
      (node (ref "ZED1") (pin "166") (pinfunction "GND_166") (pintype "power_in"))
      (node (ref "ZED1") (pin "171") (pinfunction "GND_171") (pintype "power_in"))
      (node (ref "ZED1") (pin "172") (pinfunction "GND_172") (pintype "power_in"))
      (node (ref "ZED1") (pin "177") (pinfunction "GND_177") (pintype "power_in"))
      (node (ref "ZED1") (pin "185") (pinfunction "GND_185") (pintype "power_in"))
      (node (ref "ZED1") (pin "186") (pinfunction "GND_186") (pintype "power_in"))
      (node (ref "ZED1") (pin "191") (pinfunction "GND_191") (pintype "power_in"))
      (node (ref "ZED1") (pin "192") (pinfunction "GND_192") (pintype "power_in"))
      (node (ref "ZED1") (pin "21") (pinfunction "GND_21") (pintype "power_in"))
      (node (ref "ZED1") (pin "22") (pinfunction "GND_22") (pintype "power_in"))
      (node (ref "ZED1") (pin "27") (pinfunction "GND_27") (pintype "power_in"))
      (node (ref "ZED1") (pin "28") (pinfunction "GND_28") (pintype "power_in"))
      (node (ref "ZED1") (pin "33") (pinfunction "GND_33") (pintype "power_in"))
      (node (ref "ZED1") (pin "34") (pinfunction "GND_34") (pintype "power_in"))
      (node (ref "ZED1") (pin "39") (pinfunction "GND_39") (pintype "power_in"))
      (node (ref "ZED1") (pin "40") (pinfunction "GND_40") (pintype "power_in"))
      (node (ref "ZED1") (pin "45") (pinfunction "GND_45") (pintype "power_in"))
      (node (ref "ZED1") (pin "46") (pinfunction "GND_46") (pintype "power_in"))
      (node (ref "ZED1") (pin "51") (pinfunction "GND_51") (pintype "power_in"))
      (node (ref "ZED1") (pin "52") (pinfunction "GND_52") (pintype "power_in"))
      (node (ref "ZED1") (pin "65") (pinfunction "GND_65") (pintype "power_in"))
      (node (ref "ZED1") (pin "66") (pinfunction "GND_66") (pintype "power_in"))
      (node (ref "ZED1") (pin "71") (pinfunction "GND_71") (pintype "power_in"))
      (node (ref "ZED1") (pin "72") (pinfunction "GND_72") (pintype "power_in"))
      (node (ref "ZED1") (pin "77") (pinfunction "GND_77") (pintype "power_in"))
      (node (ref "ZED1") (pin "85") (pinfunction "GND_85") (pintype "power_in"))
      (node (ref "ZED1") (pin "86") (pinfunction "GND_86") (pintype "power_in"))
      (node (ref "ZED1") (pin "95") (pinfunction "GND_95") (pintype "power_in"))
      (node (ref "ZED1") (pin "96") (pinfunction "GND_96") (pintype "power_in"))
    )
    (net (code "7") (name "Net-(FB1-P$1)") (class "Default")
      (node (ref "C4") (pin "1") (pinfunction "1_1") (pintype "passive"))
      (node (ref "FB1") (pin "1") (pinfunction "P$1_1") (pintype "passive"))
      (node (ref "U3") (pin "5") (pinfunction "VCC_5") (pintype "power_in"))
      (node (ref "USB") (pin "VBUS") (pinfunction "VBUS_VBUS") (pintype "bidirectional"))
    )
    (net (code "8") (name "Net-(FB1-P$2)") (class "Default")
      (node (ref "FB1") (pin "2") (pinfunction "P$2_2") (pintype "passive"))
      (node (ref "U1") (pin "40") (pinfunction "VREGIN_40") (pintype "power_in"))
    )
    (net (code "9") (name "Net-(PAD1-P)") (class "Default")
      (node (ref "PAD1") (pin "1") (pinfunction "P_1") (pintype "passive"))
      (node (ref "ZED1") (pin "126") (pinfunction "_N_126") (pintype "bidirectional"))
    )
    (net (code "10") (name "Net-(PAD2-P)") (class "Default")
      (node (ref "PAD2") (pin "1") (pinfunction "P_1") (pintype "passive"))
      (node (ref "ZED1") (pin "124") (pinfunction "_P_124") (pintype "bidirectional"))
    )
    (net (code "11") (name "Net-(PAD3-P)") (class "Default")
      (node (ref "PAD3") (pin "1") (pinfunction "P_1") (pintype "passive"))
      (node (ref "ZED1") (pin "120") (pinfunction "_N_120") (pintype "bidirectional"))
    )
    (net (code "12") (name "Net-(PAD4-P)") (class "Default")
      (node (ref "PAD4") (pin "1") (pinfunction "P_1") (pintype "passive"))
      (node (ref "ZED1") (pin "118") (pinfunction "_P_118") (pintype "bidirectional"))
    )
    (net (code "13") (name "Net-(PAD7-P)") (class "Default")
      (node (ref "PAD7") (pin "1") (pinfunction "P_1") (pintype "passive"))
      (node (ref "ZED1") (pin "119") (pinfunction "_N_119") (pintype "bidirectional"))
    )
    (net (code "14") (name "Net-(PAD8-P)") (class "Default")
      (node (ref "PAD8") (pin "1") (pinfunction "P_1") (pintype "passive"))
      (node (ref "ZED1") (pin "117") (pinfunction "_P_117") (pintype "bidirectional"))
    )
    (net (code "15") (name "Net-(PAD9-P)") (class "Default")
      (node (ref "PAD9") (pin "1") (pinfunction "P_1") (pintype "passive"))
      (node (ref "ZED1") (pin "141") (pinfunction "_P_141") (pintype "bidirectional"))
    )
    (net (code "16") (name "Net-(PAD10-P)") (class "Default")
      (node (ref "PAD10") (pin "1") (pinfunction "P_1") (pintype "passive"))
      (node (ref "ZED1") (pin "143") (pinfunction "_N_143") (pintype "bidirectional"))
    )
    (net (code "17") (name "Net-(PAD13-P)") (class "Default")
      (node (ref "PAD13") (pin "1") (pinfunction "P_1") (pintype "passive"))
      (node (ref "ZED1") (pin "190") (pinfunction "_N_190") (pintype "bidirectional"))
    )
    (net (code "18") (name "Net-(PAD14-P)") (class "Default")
      (node (ref "PAD14") (pin "1") (pinfunction "P_1") (pintype "passive"))
      (node (ref "ZED1") (pin "188") (pinfunction "_P_188") (pintype "bidirectional"))
    )
    (net (code "19") (name "Net-(PAD15-P)") (class "Default")
      (node (ref "PAD15") (pin "1") (pinfunction "P_1") (pintype "passive"))
      (node (ref "ZED1") (pin "184") (pinfunction "_N_184") (pintype "bidirectional"))
    )
    (net (code "20") (name "Net-(PAD16-P)") (class "Default")
      (node (ref "PAD16") (pin "1") (pinfunction "P_1") (pintype "passive"))
      (node (ref "ZED1") (pin "182") (pinfunction "_P_182") (pintype "bidirectional"))
    )
    (net (code "21") (name "Net-(PAD19-P)") (class "Default")
      (node (ref "PAD19") (pin "1") (pinfunction "P_1") (pintype "passive"))
      (node (ref "ZED1") (pin "193") (pinfunction "_P_193") (pintype "bidirectional"))
    )
    (net (code "22") (name "Net-(PAD20-P)") (class "Default")
      (node (ref "PAD20") (pin "1") (pinfunction "P_1") (pintype "passive"))
      (node (ref "ZED1") (pin "195") (pinfunction "_N_195") (pintype "bidirectional"))
    )
    (net (code "23") (name "Net-(PAD21-P)") (class "Default")
      (node (ref "PAD21") (pin "1") (pinfunction "P_1") (pintype "passive"))
      (node (ref "ZED1") (pin "199") (pinfunction "_N_199") (pintype "bidirectional"))
    )
    (net (code "24") (name "Net-(PAD22-P)") (class "Default")
      (node (ref "PAD22") (pin "1") (pinfunction "P_1") (pintype "passive"))
      (node (ref "ZED1") (pin "197") (pinfunction "_P_197") (pintype "bidirectional"))
    )
    (net (code "25") (name "Net-(PAD25-P)") (class "Default")
      (node (ref "PAD25") (pin "1") (pinfunction "P_1") (pintype "passive"))
      (node (ref "ZED1") (pin "90") (pinfunction "_N_90") (pintype "bidirectional"))
    )
    (net (code "26") (name "Net-(PAD26-P)") (class "Default")
      (node (ref "PAD26") (pin "1") (pinfunction "P_1") (pintype "passive"))
      (node (ref "ZED1") (pin "88") (pinfunction "_P_88") (pintype "bidirectional"))
    )
    (net (code "27") (name "Net-(PAD27-P)") (class "Default")
      (node (ref "PAD27") (pin "1") (pinfunction "P_1") (pintype "passive"))
      (node (ref "ZED1") (pin "91") (pinfunction "_P_91") (pintype "bidirectional"))
    )
    (net (code "28") (name "Net-(PAD28-P)") (class "Default")
      (node (ref "PAD28") (pin "1") (pinfunction "P_1") (pintype "passive"))
      (node (ref "ZED1") (pin "93") (pinfunction "_N_93") (pintype "bidirectional"))
    )
    (net (code "29") (name "Net-(PAD31-P)") (class "Default")
      (node (ref "PAD31") (pin "1") (pinfunction "P_1") (pintype "passive"))
      (node (ref "ZED1") (pin "92") (pinfunction "_P_92") (pintype "bidirectional"))
    )
    (net (code "30") (name "Net-(PAD32-P)") (class "Default")
      (node (ref "PAD32") (pin "1") (pinfunction "P_1") (pintype "passive"))
      (node (ref "ZED1") (pin "94") (pinfunction "_N_94") (pintype "bidirectional"))
    )
    (net (code "31") (name "Net-(PAD33-P)") (class "Default")
      (node (ref "PAD33") (pin "1") (pinfunction "P_1") (pintype "passive"))
      (node (ref "ZED1") (pin "87") (pinfunction "_P_87") (pintype "bidirectional"))
    )
    (net (code "32") (name "Net-(PAD34-P)") (class "Default")
      (node (ref "PAD34") (pin "1") (pinfunction "P_1") (pintype "passive"))
      (node (ref "ZED1") (pin "89") (pinfunction "_N_89") (pintype "bidirectional"))
    )
    (net (code "33") (name "Net-(PAD37-P)") (class "Default")
      (node (ref "PAD37") (pin "1") (pinfunction "P_1") (pintype "passive"))
      (node (ref "ZED1") (pin "20") (pinfunction "_N_20") (pintype "bidirectional"))
    )
    (net (code "34") (name "Net-(PAD38-P)") (class "Default")
      (node (ref "PAD38") (pin "1") (pinfunction "P_1") (pintype "passive"))
      (node (ref "ZED1") (pin "18") (pinfunction "_P_18") (pintype "bidirectional"))
    )
    (net (code "35") (name "Net-(PAD39-P)") (class "Default")
      (node (ref "PAD39") (pin "1") (pinfunction "P_1") (pintype "passive"))
      (node (ref "ZED1") (pin "14") (pinfunction "_N_14") (pintype "bidirectional"))
    )
    (net (code "36") (name "Net-(PAD40-P)") (class "Default")
      (node (ref "PAD40") (pin "1") (pinfunction "P_1") (pintype "passive"))
      (node (ref "ZED1") (pin "12") (pinfunction "_P_12") (pintype "bidirectional"))
    )
    (net (code "37") (name "Net-(PAD43-P)") (class "Default")
      (node (ref "PAD43") (pin "1") (pinfunction "P_1") (pintype "passive"))
      (node (ref "ZED1") (pin "19") (pinfunction "_N_19") (pintype "bidirectional"))
    )
    (net (code "38") (name "Net-(PAD44-P)") (class "Default")
      (node (ref "PAD44") (pin "1") (pinfunction "P_1") (pintype "passive"))
      (node (ref "ZED1") (pin "17") (pinfunction "_P_17") (pintype "bidirectional"))
    )
    (net (code "39") (name "Net-(PAD45-P)") (class "Default")
      (node (ref "PAD45") (pin "1") (pinfunction "P_1") (pintype "passive"))
      (node (ref "ZED1") (pin "13") (pinfunction "_N_13") (pintype "bidirectional"))
    )
    (net (code "40") (name "Net-(PAD46-P)") (class "Default")
      (node (ref "PAD46") (pin "1") (pinfunction "P_1") (pintype "passive"))
      (node (ref "ZED1") (pin "11") (pinfunction "_P_11") (pintype "bidirectional"))
    )
    (net (code "41") (name "Net-(Q1-2)") (class "Default")
      (node (ref "C2") (pin "1") (pinfunction "1_1") (pintype "passive"))
      (node (ref "Q1") (pin "3") (pinfunction "2_3") (pintype "passive"))
      (node (ref "U1") (pin "2") (pinfunction "OSCO_2") (pintype "output"))
    )
    (net (code "42") (name "Net-(U1-DM)") (class "Default")
      (node (ref "U1") (pin "6") (pinfunction "DM_6") (pintype "bidirectional"))
      (node (ref "U3") (pin "2") (pinfunction "IO2_2") (pintype "bidirectional"))
      (node (ref "USB") (pin "D-") (pinfunction "D-_D-") (pintype "bidirectional"))
    )
    (net (code "43") (name "Net-(U1-DP)") (class "Default")
      (node (ref "U1") (pin "7") (pinfunction "DP_7") (pintype "bidirectional"))
      (node (ref "U3") (pin "1") (pinfunction "IO1_1") (pintype "bidirectional"))
      (node (ref "USB") (pin "D+") (pinfunction "D+_D+") (pintype "bidirectional"))
    )
    (net (code "44") (name "Net-(U1-EECLK)") (class "Default")
      (node (ref "R4") (pin "1") (pinfunction "1_1") (pintype "passive"))
      (node (ref "U1") (pin "44") (pinfunction "EECLK_44") (pintype "output"))
      (node (ref "U2") (pin "4") (pinfunction "CLK_4") (pintype "input"))
    )
    (net (code "45") (name "Net-(U1-EECS)") (class "Default")
      (node (ref "R3") (pin "1") (pinfunction "1_1") (pintype "passive"))
      (node (ref "U1") (pin "45") (pinfunction "EECS_45") (pintype "output"))
      (node (ref "U2") (pin "5") (pinfunction "CS_5") (pintype "input"))
    )
    (net (code "46") (name "Net-(U1-EEDATA)") (class "Default")
      (node (ref "R6") (pin "2") (pinfunction "2_2") (pintype "passive"))
      (node (ref "U1") (pin "43") (pinfunction "EEDATA_43") (pintype "bidirectional"))
      (node (ref "U2") (pin "3") (pinfunction "DI_3") (pintype "input"))
    )
    (net (code "47") (name "Net-(U1-OSCI)") (class "Default")
      (node (ref "C1") (pin "1") (pinfunction "1_1") (pintype "passive"))
      (node (ref "Q1") (pin "1") (pinfunction "1_1") (pintype "passive"))
      (node (ref "U1") (pin "1") (pinfunction "OSCI_1") (pintype "input"))
    )
    (net (code "48") (name "Net-(U1-REF)") (class "Default")
      (node (ref "R1") (pin "2") (pinfunction "2_2") (pintype "passive"))
      (node (ref "U1") (pin "5") (pinfunction "REF_5") (pintype "input"))
    )
    (net (code "49") (name "Net-(U1-RESET#)") (class "Default")
      (node (ref "C3") (pin "1") (pinfunction "1_1") (pintype "passive"))
      (node (ref "R2") (pin "1") (pinfunction "1_1") (pintype "passive"))
      (node (ref "U1") (pin "34") (pinfunction "RESET#_34") (pintype "input"))
    )
    (net (code "50") (name "Net-(U2-DO)") (class "Default")
      (node (ref "R5") (pin "1") (pinfunction "1_1") (pintype "passive"))
      (node (ref "R6") (pin "1") (pinfunction "1_1") (pintype "passive"))
      (node (ref "U2") (pin "1") (pinfunction "DO_1") (pintype "output"))
    )
    (net (code "51") (name "Net-(U3-IO3)") (class "Default")
      (node (ref "U3") (pin "4") (pinfunction "IO3_4") (pintype "bidirectional"))
      (node (ref "USB") (pin "ID") (pinfunction "USBID_ID") (pintype "bidirectional"))
    )
    (net (code "52") (name "Net-(X1-A)") (class "Default")
      (node (ref "X1") (pin "2") (pinfunction "A_2") (pintype "bidirectional"))
      (node (ref "ZED1") (pin "29") (pinfunction "_P_29") (pintype "bidirectional"))
    )
    (net (code "53") (name "Net-(X1-B)") (class "Default")
      (node (ref "X1") (pin "6") (pinfunction "B_6") (pintype "bidirectional"))
      (node (ref "ZED1") (pin "23") (pinfunction "_P_23") (pintype "bidirectional"))
    )
    (net (code "54") (name "Net-(X1-~{A})") (class "Default")
      (node (ref "X1") (pin "3") (pinfunction "~{A}_3") (pintype "bidirectional"))
      (node (ref "ZED1") (pin "31") (pinfunction "_N_31") (pintype "bidirectional"))
    )
    (net (code "55") (name "Net-(X1-~{B})") (class "Default")
      (node (ref "X1") (pin "5") (pinfunction "~{B}_5") (pintype "bidirectional"))
      (node (ref "ZED1") (pin "25") (pinfunction "_N_25") (pintype "bidirectional"))
    )
    (net (code "56") (name "Net-(X2-A)") (class "Default")
      (node (ref "X2") (pin "2") (pinfunction "A_2") (pintype "bidirectional"))
      (node (ref "ZED1") (pin "24") (pinfunction "_P_24") (pintype "bidirectional"))
    )
    (net (code "57") (name "Net-(X2-B)") (class "Default")
      (node (ref "X2") (pin "6") (pinfunction "B_6") (pintype "bidirectional"))
      (node (ref "ZED1") (pin "30") (pinfunction "_P_30") (pintype "bidirectional"))
    )
    (net (code "58") (name "Net-(X2-~{A})") (class "Default")
      (node (ref "X2") (pin "3") (pinfunction "~{A}_3") (pintype "bidirectional"))
      (node (ref "ZED1") (pin "26") (pinfunction "_N_26") (pintype "bidirectional"))
    )
    (net (code "59") (name "Net-(X2-~{B})") (class "Default")
      (node (ref "X2") (pin "5") (pinfunction "~{B}_5") (pintype "bidirectional"))
      (node (ref "ZED1") (pin "32") (pinfunction "_N_32") (pintype "bidirectional"))
    )
    (net (code "60") (name "Net-(X3-A)") (class "Default")
      (node (ref "X3") (pin "2") (pinfunction "A_2") (pintype "bidirectional"))
      (node (ref "ZED1") (pin "41") (pinfunction "_P_41") (pintype "bidirectional"))
    )
    (net (code "61") (name "Net-(X3-B)") (class "Default")
      (node (ref "X3") (pin "6") (pinfunction "B_6") (pintype "bidirectional"))
      (node (ref "ZED1") (pin "36") (pinfunction "_P_36") (pintype "bidirectional"))
    )
    (net (code "62") (name "Net-(X3-~{A})") (class "Default")
      (node (ref "X3") (pin "3") (pinfunction "~{A}_3") (pintype "bidirectional"))
      (node (ref "ZED1") (pin "43") (pinfunction "_N_43") (pintype "bidirectional"))
    )
    (net (code "63") (name "Net-(X3-~{B})") (class "Default")
      (node (ref "X3") (pin "5") (pinfunction "~{B}_5") (pintype "bidirectional"))
      (node (ref "ZED1") (pin "38") (pinfunction "_N_38") (pintype "bidirectional"))
    )
    (net (code "64") (name "Net-(X4-A)") (class "Default")
      (node (ref "X4") (pin "2") (pinfunction "A_2") (pintype "bidirectional"))
      (node (ref "ZED1") (pin "130") (pinfunction "_P_130") (pintype "bidirectional"))
    )
    (net (code "65") (name "Net-(X4-B)") (class "Default")
      (node (ref "X4") (pin "6") (pinfunction "B_6") (pintype "bidirectional"))
      (node (ref "ZED1") (pin "136") (pinfunction "_P_136") (pintype "bidirectional"))
    )
    (net (code "66") (name "Net-(X4-~{A})") (class "Default")
      (node (ref "X4") (pin "3") (pinfunction "~{A}_3") (pintype "bidirectional"))
      (node (ref "ZED1") (pin "132") (pinfunction "_N_132") (pintype "bidirectional"))
    )
    (net (code "67") (name "Net-(X4-~{B})") (class "Default")
      (node (ref "X4") (pin "5") (pinfunction "~{B}_5") (pintype "bidirectional"))
      (node (ref "ZED1") (pin "138") (pinfunction "_N_138") (pintype "bidirectional"))
    )
    (net (code "68") (name "Net-(X5-A)") (class "Default")
      (node (ref "X5") (pin "2") (pinfunction "A_2") (pintype "bidirectional"))
      (node (ref "ZED1") (pin "49") (pinfunction "_N_49") (pintype "bidirectional"))
    )
    (net (code "69") (name "Net-(X5-B)") (class "Default")
      (node (ref "X5") (pin "6") (pinfunction "B_6") (pintype "bidirectional"))
      (node (ref "ZED1") (pin "53") (pinfunction "_P_53") (pintype "bidirectional"))
    )
    (net (code "70") (name "Net-(X5-~{A})") (class "Default")
      (node (ref "X5") (pin "3") (pinfunction "~{A}_3") (pintype "bidirectional"))
      (node (ref "ZED1") (pin "47") (pinfunction "_P_47") (pintype "bidirectional"))
    )
    (net (code "71") (name "Net-(X5-~{B})") (class "Default")
      (node (ref "X5") (pin "5") (pinfunction "~{B}_5") (pintype "bidirectional"))
      (node (ref "ZED1") (pin "55") (pinfunction "_N_55") (pintype "bidirectional"))
    )
    (net (code "72") (name "Net-(X6-A)") (class "Default")
      (node (ref "X6") (pin "2") (pinfunction "A_2") (pintype "bidirectional"))
      (node (ref "ZED1") (pin "42") (pinfunction "_P_42") (pintype "bidirectional"))
    )
    (net (code "73") (name "Net-(X6-B)") (class "Default")
      (node (ref "X6") (pin "6") (pinfunction "B_6") (pintype "bidirectional"))
      (node (ref "ZED1") (pin "48") (pinfunction "_P_48") (pintype "bidirectional"))
    )
    (net (code "74") (name "Net-(X6-~{A})") (class "Default")
      (node (ref "X6") (pin "3") (pinfunction "~{A}_3") (pintype "bidirectional"))
      (node (ref "ZED1") (pin "44") (pinfunction "_N_44") (pintype "bidirectional"))
    )
    (net (code "75") (name "Net-(X6-~{B})") (class "Default")
      (node (ref "X6") (pin "5") (pinfunction "~{B}_5") (pintype "bidirectional"))
      (node (ref "ZED1") (pin "50") (pinfunction "_N_50") (pintype "bidirectional"))
    )
    (net (code "76") (name "Net-(X7-A)") (class "Default")
      (node (ref "X7") (pin "2") (pinfunction "A_2") (pintype "bidirectional"))
      (node (ref "ZED1") (pin "61") (pinfunction "_P_61") (pintype "bidirectional"))
    )
    (net (code "77") (name "Net-(X7-B)") (class "Default")
      (node (ref "X7") (pin "6") (pinfunction "B_6") (pintype "bidirectional"))
      (node (ref "ZED1") (pin "54") (pinfunction "_P_54") (pintype "bidirectional"))
    )
    (net (code "78") (name "Net-(X7-~{A})") (class "Default")
      (node (ref "X7") (pin "3") (pinfunction "~{A}_3") (pintype "bidirectional"))
      (node (ref "ZED1") (pin "63") (pinfunction "_N_63") (pintype "bidirectional"))
    )
    (net (code "79") (name "Net-(X7-~{B})") (class "Default")
      (node (ref "X7") (pin "5") (pinfunction "~{B}_5") (pintype "bidirectional"))
      (node (ref "ZED1") (pin "56") (pinfunction "_N_56") (pintype "bidirectional"))
    )
    (net (code "80") (name "Net-(X8-A)") (class "Default")
      (node (ref "X8") (pin "2") (pinfunction "A_2") (pintype "bidirectional"))
      (node (ref "ZED1") (pin "154") (pinfunction "_P_154") (pintype "bidirectional"))
    )
    (net (code "81") (name "Net-(X8-B)") (class "Default")
      (node (ref "X8") (pin "6") (pinfunction "B_6") (pintype "bidirectional"))
      (node (ref "ZED1") (pin "148") (pinfunction "_P_148") (pintype "bidirectional"))
    )
    (net (code "82") (name "Net-(X8-~{A})") (class "Default")
      (node (ref "X8") (pin "3") (pinfunction "~{A}_3") (pintype "bidirectional"))
      (node (ref "ZED1") (pin "156") (pinfunction "_N_156") (pintype "bidirectional"))
    )
    (net (code "83") (name "Net-(X8-~{B})") (class "Default")
      (node (ref "X8") (pin "5") (pinfunction "~{B}_5") (pintype "bidirectional"))
      (node (ref "ZED1") (pin "150") (pinfunction "_N_150") (pintype "bidirectional"))
    )
    (net (code "84") (name "Net-(X9-A)") (class "Default")
      (node (ref "X9") (pin "2") (pinfunction "A_2") (pintype "bidirectional"))
      (node (ref "ZED1") (pin "181") (pinfunction "_P_181") (pintype "bidirectional"))
    )
    (net (code "85") (name "Net-(X9-B)") (class "Default")
      (node (ref "X9") (pin "6") (pinfunction "B_6") (pintype "bidirectional"))
      (node (ref "ZED1") (pin "174") (pinfunction "_P_174") (pintype "bidirectional"))
    )
    (net (code "86") (name "Net-(X9-~{A})") (class "Default")
      (node (ref "X9") (pin "3") (pinfunction "~{A}_3") (pintype "bidirectional"))
      (node (ref "ZED1") (pin "183") (pinfunction "_N_183") (pintype "bidirectional"))
    )
    (net (code "87") (name "Net-(X9-~{B})") (class "Default")
      (node (ref "X9") (pin "5") (pinfunction "~{B}_5") (pintype "bidirectional"))
      (node (ref "ZED1") (pin "176") (pinfunction "_N_176") (pintype "bidirectional"))
    )
    (net (code "88") (name "Net-(X10-A)") (class "Default")
      (node (ref "X10") (pin "2") (pinfunction "A_2") (pintype "bidirectional"))
      (node (ref "ZED1") (pin "74") (pinfunction "_P_74") (pintype "bidirectional"))
    )
    (net (code "89") (name "Net-(X10-B)") (class "Default")
      (node (ref "X10") (pin "6") (pinfunction "B_6") (pintype "bidirectional"))
      (node (ref "ZED1") (pin "82") (pinfunction "_P_82") (pintype "bidirectional"))
    )
    (net (code "90") (name "Net-(X10-~{A})") (class "Default")
      (node (ref "X10") (pin "3") (pinfunction "~{A}_3") (pintype "bidirectional"))
      (node (ref "ZED1") (pin "76") (pinfunction "_N_76") (pintype "bidirectional"))
    )
    (net (code "91") (name "Net-(X10-~{B})") (class "Default")
      (node (ref "X10") (pin "5") (pinfunction "~{B}_5") (pintype "bidirectional"))
      (node (ref "ZED1") (pin "84") (pinfunction "_N_84") (pintype "bidirectional"))
    )
    (net (code "92") (name "Net-(X11-A)") (class "Default")
      (node (ref "X11") (pin "2") (pinfunction "A_2") (pintype "bidirectional"))
      (node (ref "ZED1") (pin "67") (pinfunction "_P_67") (pintype "bidirectional"))
    )
    (net (code "93") (name "Net-(X11-B)") (class "Default")
      (node (ref "X11") (pin "6") (pinfunction "B_6") (pintype "bidirectional"))
      (node (ref "ZED1") (pin "73") (pinfunction "_P_73") (pintype "bidirectional"))
    )
    (net (code "94") (name "Net-(X11-~{A})") (class "Default")
      (node (ref "X11") (pin "3") (pinfunction "~{A}_3") (pintype "bidirectional"))
      (node (ref "ZED1") (pin "69") (pinfunction "_N_69") (pintype "bidirectional"))
    )
    (net (code "95") (name "Net-(X11-~{B})") (class "Default")
      (node (ref "X11") (pin "5") (pinfunction "~{B}_5") (pintype "bidirectional"))
      (node (ref "ZED1") (pin "75") (pinfunction "_N_75") (pintype "bidirectional"))
    )
    (net (code "96") (name "Net-(X12-A)") (class "Default")
      (node (ref "X12") (pin "2") (pinfunction "A_2") (pintype "bidirectional"))
      (node (ref "ZED1") (pin "62") (pinfunction "_P_62") (pintype "bidirectional"))
    )
    (net (code "97") (name "Net-(X12-B)") (class "Default")
      (node (ref "X12") (pin "6") (pinfunction "B_6") (pintype "bidirectional"))
      (node (ref "ZED1") (pin "68") (pinfunction "_P_68") (pintype "bidirectional"))
    )
    (net (code "98") (name "Net-(X12-~{A})") (class "Default")
      (node (ref "X12") (pin "3") (pinfunction "~{A}_3") (pintype "bidirectional"))
      (node (ref "ZED1") (pin "64") (pinfunction "_N_64") (pintype "bidirectional"))
    )
    (net (code "99") (name "Net-(X12-~{B})") (class "Default")
      (node (ref "X12") (pin "5") (pinfunction "~{B}_5") (pintype "bidirectional"))
      (node (ref "ZED1") (pin "70") (pinfunction "_N_70") (pintype "bidirectional"))
    )
    (net (code "100") (name "Net-(ZED1AK-_N)") (class "Default")
      (node (ref "Y6") (pin "1") (pinfunction "1_1") (pintype "passive"))
      (node (ref "ZED1") (pin "125") (pinfunction "_N_125") (pintype "bidirectional"))
    )
    (net (code "101") (name "Net-(ZED1AK-_P)") (class "Default")
      (node (ref "Y5") (pin "1") (pinfunction "1_1") (pintype "passive"))
      (node (ref "ZED1") (pin "123") (pinfunction "_P_123") (pintype "bidirectional"))
    )
    (net (code "102") (name "Net-(ZED1AR-_N)") (class "Default")
      (node (ref "Z6") (pin "1") (pinfunction "1_1") (pintype "passive"))
      (node (ref "ZED1") (pin "144") (pinfunction "_N_144") (pintype "bidirectional"))
    )
    (net (code "103") (name "Net-(ZED1AR-_P)") (class "Default")
      (node (ref "Z5") (pin "1") (pinfunction "1_1") (pintype "passive"))
      (node (ref "ZED1") (pin "142") (pinfunction "_P_142") (pintype "bidirectional"))
    )
    (net (code "104") (name "Net-(ZED1AX-_N)") (class "Default")
      (node (ref "Z4") (pin "1") (pinfunction "1_1") (pintype "passive"))
      (node (ref "ZED1") (pin "164") (pinfunction "_N_164") (pintype "bidirectional"))
    )
    (net (code "105") (name "Net-(ZED1AX-_P)") (class "Default")
      (node (ref "Z3") (pin "1") (pinfunction "1_1") (pintype "passive"))
      (node (ref "ZED1") (pin "162") (pinfunction "_P_162") (pintype "bidirectional"))
    )
    (net (code "106") (name "Net-(ZED1AY-_N)") (class "Default")
      (node (ref "Y4") (pin "1") (pinfunction "1_1") (pintype "passive"))
      (node (ref "ZED1") (pin "169") (pinfunction "_N_169") (pintype "bidirectional"))
    )
    (net (code "107") (name "Net-(ZED1AY-_P)") (class "Default")
      (node (ref "Y3") (pin "1") (pinfunction "1_1") (pintype "passive"))
      (node (ref "ZED1") (pin "167") (pinfunction "_P_167") (pintype "bidirectional"))
    )
    (net (code "108") (name "Net-(ZED1AZ-_N)") (class "Default")
      (node (ref "Z1") (pin "1") (pinfunction "1_1") (pintype "passive"))
      (node (ref "ZED1") (pin "170") (pinfunction "_N_170") (pintype "bidirectional"))
    )
    (net (code "109") (name "Net-(ZED1AZ-_P)") (class "Default")
      (node (ref "Z2") (pin "1") (pinfunction "1_1") (pintype "passive"))
      (node (ref "ZED1") (pin "168") (pinfunction "_P_168") (pintype "bidirectional"))
    )
    (net (code "110") (name "Net-(ZED1BA-_N)") (class "Default")
      (node (ref "Y1") (pin "1") (pinfunction "1_1") (pintype "passive"))
      (node (ref "ZED1") (pin "175") (pinfunction "_N_175") (pintype "bidirectional"))
    )
    (net (code "111") (name "Net-(ZED1BA-_P)") (class "Default")
      (node (ref "Y2") (pin "1") (pinfunction "1_1") (pintype "passive"))
      (node (ref "ZED1") (pin "173") (pinfunction "_P_173") (pintype "bidirectional"))
    )
    (net (code "112") (name "PMOD_A_VCC") (class "Default")
      (node (ref "JP1") (pin "1") (pinfunction "1_1") (pintype "passive"))
      (node (ref "PAD12") (pin "1") (pinfunction "P_1") (pintype "passive"))
      (node (ref "PAD6") (pin "1") (pinfunction "P_1") (pintype "passive"))
    )
    (net (code "113") (name "PMOD_B_VCC") (class "Default")
      (node (ref "JP2") (pin "1") (pinfunction "1_1") (pintype "passive"))
      (node (ref "PAD18") (pin "1") (pinfunction "P_1") (pintype "passive"))
      (node (ref "PAD24") (pin "1") (pinfunction "P_1") (pintype "passive"))
    )
    (net (code "114") (name "PMOD_C_VCC") (class "Default")
      (node (ref "JP3") (pin "2") (pinfunction "2_2") (pintype "passive"))
      (node (ref "PAD30") (pin "1") (pinfunction "P_1") (pintype "passive"))
      (node (ref "PAD36") (pin "1") (pinfunction "P_1") (pintype "passive"))
    )
    (net (code "115") (name "PMOD_D_VCC") (class "Default")
      (node (ref "JP4") (pin "2") (pinfunction "2_2") (pintype "passive"))
      (node (ref "PAD42") (pin "1") (pinfunction "P_1") (pintype "passive"))
      (node (ref "PAD48") (pin "1") (pinfunction "P_1") (pintype "passive"))
    )
    (net (code "116") (name "VCCA") (class "Default")
      (node (ref "C6") (pin "1") (pinfunction "1_1") (pintype "passive"))
      (node (ref "U1") (pin "37") (pinfunction "VCCA_37") (pintype "output"))
    )
    (net (code "117") (name "VCCD") (class "Default")
      (node (ref "FB2") (pin "1") (pinfunction "P$1_1") (pintype "passive"))
      (node (ref "FB3") (pin "1") (pinfunction "P$1_1") (pintype "passive"))
      (node (ref "R2") (pin "2") (pinfunction "2_2") (pintype "passive"))
      (node (ref "R3") (pin "2") (pinfunction "2_2") (pintype "passive"))
      (node (ref "R4") (pin "2") (pinfunction "2_2") (pintype "passive"))
      (node (ref "R5") (pin "2") (pinfunction "2_2") (pintype "passive"))
      (node (ref "U1") (pin "12") (pinfunction "VCCIO_12") (pintype "power_in"))
      (node (ref "U1") (pin "24") (pinfunction "VCCIO_24") (pintype "power_in"))
      (node (ref "U1") (pin "39") (pinfunction "VCCD_39") (pintype "power_in"))
      (node (ref "U1") (pin "46") (pinfunction "VCCIO_46") (pintype "power_in"))
      (node (ref "U2") (pin "6") (pinfunction "VCC_6") (pintype "power_in"))
    )
    (net (code "118") (name "VCCO_13") (class "Default")
      (node (ref "JP2") (pin "2") (pinfunction "2_2") (pintype "passive"))
      (node (ref "ZED1") (pin "198") (pinfunction "VCCO_13_198") (pintype "power_in"))
    )
    (net (code "119") (name "VCCO_34") (class "Default")
      (node (ref "JP3") (pin "1") (pinfunction "1_1") (pintype "passive"))
      (node (ref "ZED1") (pin "78") (pinfunction "VCCO_34_78") (pintype "power_in"))
      (node (ref "ZED1") (pin "79") (pinfunction "VCCO_34_79") (pintype "power_in"))
      (node (ref "ZED1") (pin "80") (pinfunction "VCCO_34_80") (pintype "power_in"))
    )
    (net (code "120") (name "VCCO_35") (class "Default")
      (node (ref "JP2") (pin "3") (pinfunction "3_3") (pintype "passive"))
      (node (ref "ZED1") (pin "178") (pinfunction "VCCO_35_178") (pintype "power_in"))
      (node (ref "ZED1") (pin "179") (pinfunction "VCCO_35_179") (pintype "power_in"))
      (node (ref "ZED1") (pin "180") (pinfunction "VCCO_35_180") (pintype "power_in"))
    )
    (net (code "121") (name "VCORE") (class "Default")
      (node (ref "C5") (pin "1") (pinfunction "1_1") (pintype "passive"))
      (node (ref "U1") (pin "38") (pinfunction "VCORE_38") (pintype "output"))
    )
    (net (code "122") (name "VIN_HDR") (class "Default")
      (node (ref "JP1") (pin "2") (pinfunction "2_2") (pintype "passive"))
      (node (ref "JP4") (pin "1") (pinfunction "1_1") (pintype "passive"))
      (node (ref "ZED1") (pin "112") (pinfunction "VIN_HDR_112") (pintype "power_in"))
      (node (ref "ZED1") (pin "157") (pinfunction "VIN_HDR_157") (pintype "power_in"))
      (node (ref "ZED1") (pin "158") (pinfunction "VIN_HDR_158") (pintype "power_in"))
      (node (ref "ZED1") (pin "159") (pinfunction "VIN_HDR_159") (pintype "power_in"))
      (node (ref "ZED1") (pin "160") (pinfunction "VIN_HDR_160") (pintype "power_in"))
      (node (ref "ZED1") (pin "57") (pinfunction "VIN_HDR_57") (pintype "power_in"))
      (node (ref "ZED1") (pin "58") (pinfunction "VIN_HDR_58") (pintype "power_in"))
      (node (ref "ZED1") (pin "59") (pinfunction "VIN_HDR_59") (pintype "power_in"))
      (node (ref "ZED1") (pin "60") (pinfunction "VIN_HDR_60") (pintype "power_in"))
    )
    (net (code "123") (name "VPHY") (class "Default")
      (node (ref "C7") (pin "1") (pinfunction "1_1") (pintype "passive"))
      (node (ref "C8") (pin "1") (pinfunction "1_1") (pintype "passive"))
      (node (ref "FB2") (pin "2") (pinfunction "P$2_2") (pintype "passive"))
      (node (ref "U1") (pin "3") (pinfunction "VPHY_3") (pintype "power_in"))
    )
    (net (code "124") (name "VPLL") (class "Default")
      (node (ref "C10") (pin "1") (pinfunction "1_1") (pintype "passive"))
      (node (ref "C9") (pin "1") (pinfunction "1_1") (pintype "passive"))
      (node (ref "FB3") (pin "2") (pinfunction "P$2_2") (pintype "passive"))
      (node (ref "U1") (pin "8") (pinfunction "VPLL_8") (pintype "power_in"))
    )
    (net (code "125") (name "unconnected-(U1-ACBUS0-Pad21)") (class "Default")
      (node (ref "U1") (pin "21") (pinfunction "ACBUS0_21") (pintype "bidirectional"))
    )
    (net (code "126") (name "unconnected-(U1-ACBUS1-Pad25)") (class "Default")
      (node (ref "U1") (pin "25") (pinfunction "ACBUS1_25") (pintype "bidirectional"))
    )
    (net (code "127") (name "unconnected-(U1-ACBUS2-Pad26)") (class "Default")
      (node (ref "U1") (pin "26") (pinfunction "ACBUS2_26") (pintype "bidirectional"))
    )
    (net (code "128") (name "unconnected-(U1-ACBUS3-Pad27)") (class "Default")
      (node (ref "U1") (pin "27") (pinfunction "ACBUS3_27") (pintype "bidirectional"))
    )
    (net (code "129") (name "unconnected-(U1-ACBUS4-Pad28)") (class "Default")
      (node (ref "U1") (pin "28") (pinfunction "ACBUS4_28") (pintype "bidirectional"))
    )
    (net (code "130") (name "unconnected-(U1-ACBUS5-Pad29)") (class "Default")
      (node (ref "U1") (pin "29") (pinfunction "ACBUS5_29") (pintype "bidirectional"))
    )
    (net (code "131") (name "unconnected-(U1-ACBUS6-Pad30)") (class "Default")
      (node (ref "U1") (pin "30") (pinfunction "ACBUS6_30") (pintype "bidirectional"))
    )
    (net (code "132") (name "unconnected-(U1-ACBUS7-Pad31)") (class "Default")
      (node (ref "U1") (pin "31") (pinfunction "ACBUS7_31") (pintype "bidirectional"))
    )
    (net (code "133") (name "unconnected-(U1-ACBUS8-Pad32)") (class "Default")
      (node (ref "U1") (pin "32") (pinfunction "ACBUS8_32") (pintype "bidirectional"))
    )
    (net (code "134") (name "unconnected-(U1-ACBUS9-Pad33)") (class "Default")
      (node (ref "U1") (pin "33") (pinfunction "ACBUS9_33") (pintype "bidirectional"))
    )
    (net (code "135") (name "unconnected-(U1-ADBUS4-Pad17)") (class "Default")
      (node (ref "U1") (pin "17") (pinfunction "ADBUS4_17") (pintype "output"))
    )
    (net (code "136") (name "unconnected-(U1-ADBUS5-Pad18)") (class "Default")
      (node (ref "U1") (pin "18") (pinfunction "ADBUS5_18") (pintype "input"))
    )
    (net (code "137") (name "unconnected-(U1-ADBUS6-Pad19)") (class "Default")
      (node (ref "U1") (pin "19") (pinfunction "ADBUS6_19") (pintype "input"))
    )
    (net (code "138") (name "unconnected-(U1-ADBUS7-Pad20)") (class "Default")
      (node (ref "U1") (pin "20") (pinfunction "ADBUS7_20") (pintype "input"))
    )
    (net (code "139") (name "unconnected-(U1-TEST-Pad42)") (class "Default")
      (node (ref "U1") (pin "42") (pinfunction "TEST_42") (pintype "input"))
    )
    (net (code "140") (name "unconnected-(ZED1AF-_N-Pad83)") (class "Default")
      (node (ref "ZED1") (pin "83") (pinfunction "_N_83") (pintype "bidirectional"))
    )
    (net (code "141") (name "unconnected-(ZED1AF-_P-Pad81)") (class "Default")
      (node (ref "ZED1") (pin "81") (pinfunction "_P_81") (pintype "bidirectional"))
    )
    (net (code "142") (name "unconnected-(ZED1AH-_0-Pad9)") (class "Default")
      (node (ref "ZED1") (pin "9") (pinfunction "_0_9") (pintype "bidirectional"))
    )
    (net (code "143") (name "unconnected-(ZED1AH-_1-Pad10)") (class "Default")
      (node (ref "ZED1") (pin "10") (pinfunction "_1_10") (pintype "bidirectional"))
    )
    (net (code "144") (name "unconnected-(ZED1AM-_N-Pad131)") (class "Default")
      (node (ref "ZED1") (pin "131") (pinfunction "_N_131") (pintype "bidirectional"))
    )
    (net (code "145") (name "unconnected-(ZED1AM-_P-Pad129)") (class "Default")
      (node (ref "ZED1") (pin "129") (pinfunction "_P_129") (pintype "bidirectional"))
    )
    (net (code "146") (name "unconnected-(ZED1AO-_N-Pad137)") (class "Default")
      (node (ref "ZED1") (pin "137") (pinfunction "_N_137") (pintype "bidirectional"))
    )
    (net (code "147") (name "unconnected-(ZED1AO-_P-Pad135)") (class "Default")
      (node (ref "ZED1") (pin "135") (pinfunction "_P_135") (pintype "bidirectional"))
    )
    (net (code "148") (name "unconnected-(ZED1AS-_N-Pad149)") (class "Default")
      (node (ref "ZED1") (pin "149") (pinfunction "_N_149") (pintype "bidirectional"))
    )
    (net (code "149") (name "unconnected-(ZED1AS-_P-Pad147)") (class "Default")
      (node (ref "ZED1") (pin "147") (pinfunction "_P_147") (pintype "bidirectional"))
    )
    (net (code "150") (name "unconnected-(ZED1AU-_N-Pad155)") (class "Default")
      (node (ref "ZED1") (pin "155") (pinfunction "_N_155") (pintype "bidirectional"))
    )
    (net (code "151") (name "unconnected-(ZED1AU-_P-Pad153)") (class "Default")
      (node (ref "ZED1") (pin "153") (pinfunction "_P_153") (pintype "bidirectional"))
    )
    (net (code "152") (name "unconnected-(ZED1AW-_N-Pad163)") (class "Default")
      (node (ref "ZED1") (pin "163") (pinfunction "_N_163") (pintype "bidirectional"))
    )
    (net (code "153") (name "unconnected-(ZED1AW-_P-Pad161)") (class "Default")
      (node (ref "ZED1") (pin "161") (pinfunction "_P_161") (pintype "bidirectional"))
    )
    (net (code "154") (name "unconnected-(ZED1BE-_N-Pad189)") (class "Default")
      (node (ref "ZED1") (pin "189") (pinfunction "_N_189") (pintype "bidirectional"))
    )
    (net (code "155") (name "unconnected-(ZED1BE-_P-Pad187)") (class "Default")
      (node (ref "ZED1") (pin "187") (pinfunction "_P_187") (pintype "bidirectional"))
    )
    (net (code "156") (name "unconnected-(ZED1BG-_0-Pad113)") (class "Default")
      (node (ref "ZED1") (pin "113") (pinfunction "_0_113") (pintype "bidirectional"))
    )
    (net (code "157") (name "unconnected-(ZED1BG-_1-Pad114)") (class "Default")
      (node (ref "ZED1") (pin "114") (pinfunction "_1_114") (pintype "bidirectional"))
    )
    (net (code "158") (name "unconnected-(ZED1BH-_N-Pad99)") (class "Default")
      (node (ref "ZED1") (pin "99") (pinfunction "_N_99") (pintype "bidirectional"))
    )
    (net (code "159") (name "unconnected-(ZED1BH-_P-Pad97)") (class "Default")
      (node (ref "ZED1") (pin "97") (pinfunction "_P_97") (pintype "bidirectional"))
    )
    (net (code "160") (name "unconnected-(ZED1BI-FPGA_DONE-Pad8)") (class "Default")
      (node (ref "ZED1") (pin "8") (pinfunction "FPGA_DONE_8") (pintype "output"))
    )
    (net (code "161") (name "unconnected-(ZED1BI-PG_MODULE-Pad111)") (class "Default")
      (node (ref "ZED1") (pin "111") (pinfunction "PG_MODULE_111") (pintype "output"))
    )
    (net (code "162") (name "unconnected-(ZED1BI-PWR_ENABLE-Pad5)") (class "Default")
      (node (ref "ZED1") (pin "5") (pinfunction "PWR_ENABLE_5") (pintype "input"))
    )
    (net (code "163") (name "unconnected-(ZED1BI-~{CARRIER_SRST}-Pad6)") (class "Default")
      (node (ref "ZED1") (pin "6") (pinfunction "~{CARRIER_SRST}_6") (pintype "output"))
    )
    (net (code "164") (name "unconnected-(ZED1BI-~{INIT}-Pad109)") (class "Default")
      (node (ref "ZED1") (pin "109") (pinfunction "~{INIT}_109") (pintype "input"))
    )
    (net (code "165") (name "unconnected-(ZED1BI-~{PROGRAM}-Pad110)") (class "Default")
      (node (ref "ZED1") (pin "110") (pinfunction "~{PROGRAM}_110") (pintype "input"))
    )
    (net (code "166") (name "unconnected-(ZED1F-_N-Pad196)") (class "Default")
      (node (ref "ZED1") (pin "196") (pinfunction "_N_196") (pintype "bidirectional"))
    )
    (net (code "167") (name "unconnected-(ZED1F-_P-Pad194)") (class "Default")
      (node (ref "ZED1") (pin "194") (pinfunction "_P_194") (pintype "bidirectional"))
    )
    (net (code "168") (name "unconnected-(ZED1H-_0-Pad200)") (class "Default")
      (node (ref "ZED1") (pin "200") (pinfunction "_0_200") (pintype "bidirectional"))
    )
    (net (code "169") (name "unconnected-(ZED1I-_N-Pad100)") (class "Default")
      (node (ref "ZED1") (pin "100") (pinfunction "_N_100") (pintype "bidirectional"))
    )
    (net (code "170") (name "unconnected-(ZED1I-_P-Pad98)") (class "Default")
      (node (ref "ZED1") (pin "98") (pinfunction "_P_98") (pintype "bidirectional"))
    )
    (net (code "171") (name "unconnected-(ZED1R-_N-Pad37)") (class "Default")
      (node (ref "ZED1") (pin "37") (pinfunction "_N_37") (pintype "bidirectional"))
    )
    (net (code "172") (name "unconnected-(ZED1R-_P-Pad35)") (class "Default")
      (node (ref "ZED1") (pin "35") (pinfunction "_P_35") (pintype "bidirectional"))
    )
  )
)
